# STM32F103ZET6.net
KiCad netlist of a schematic drawn in Altium Designer
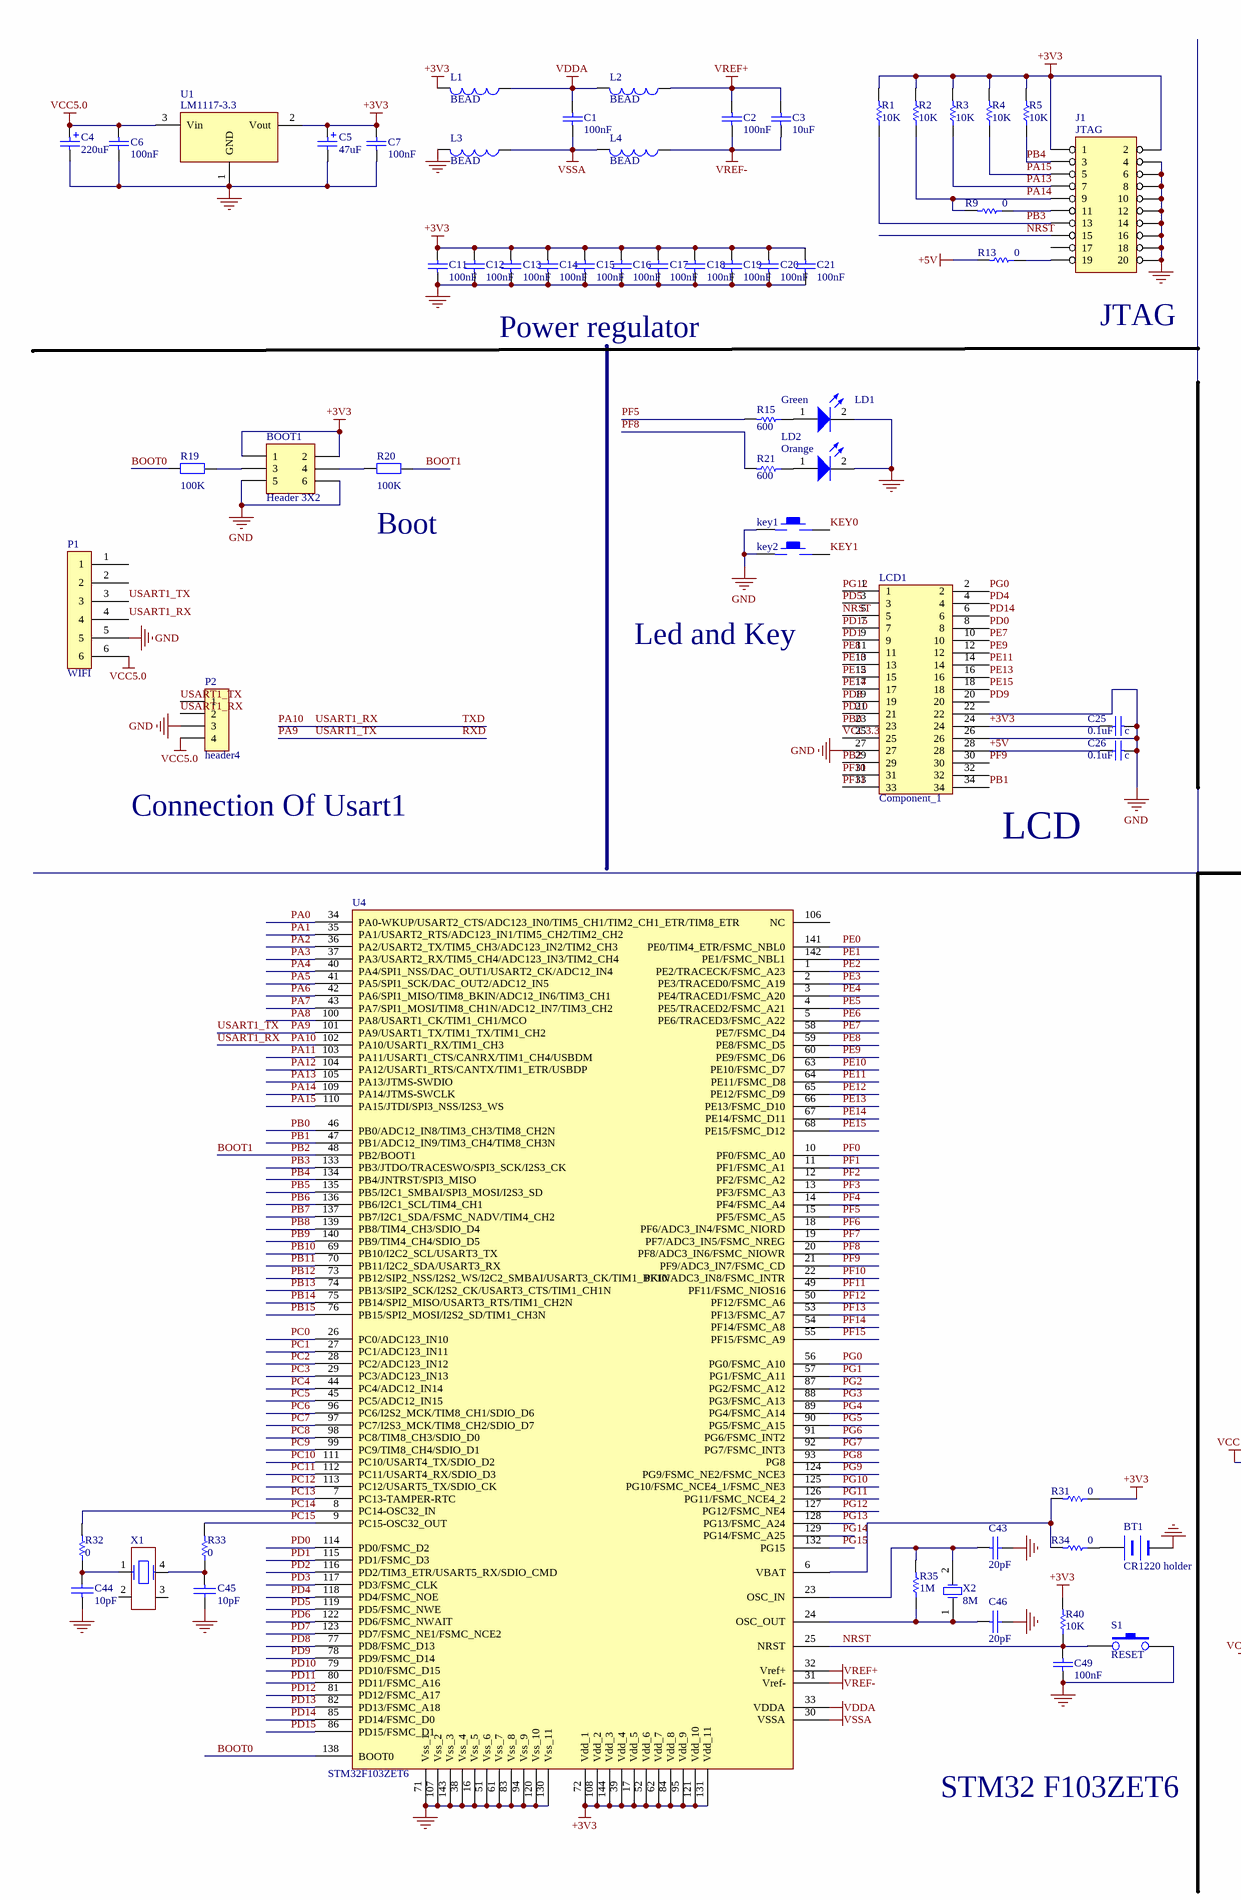
[diagram p0: STM32F103ZET6.SCHDOC, left]
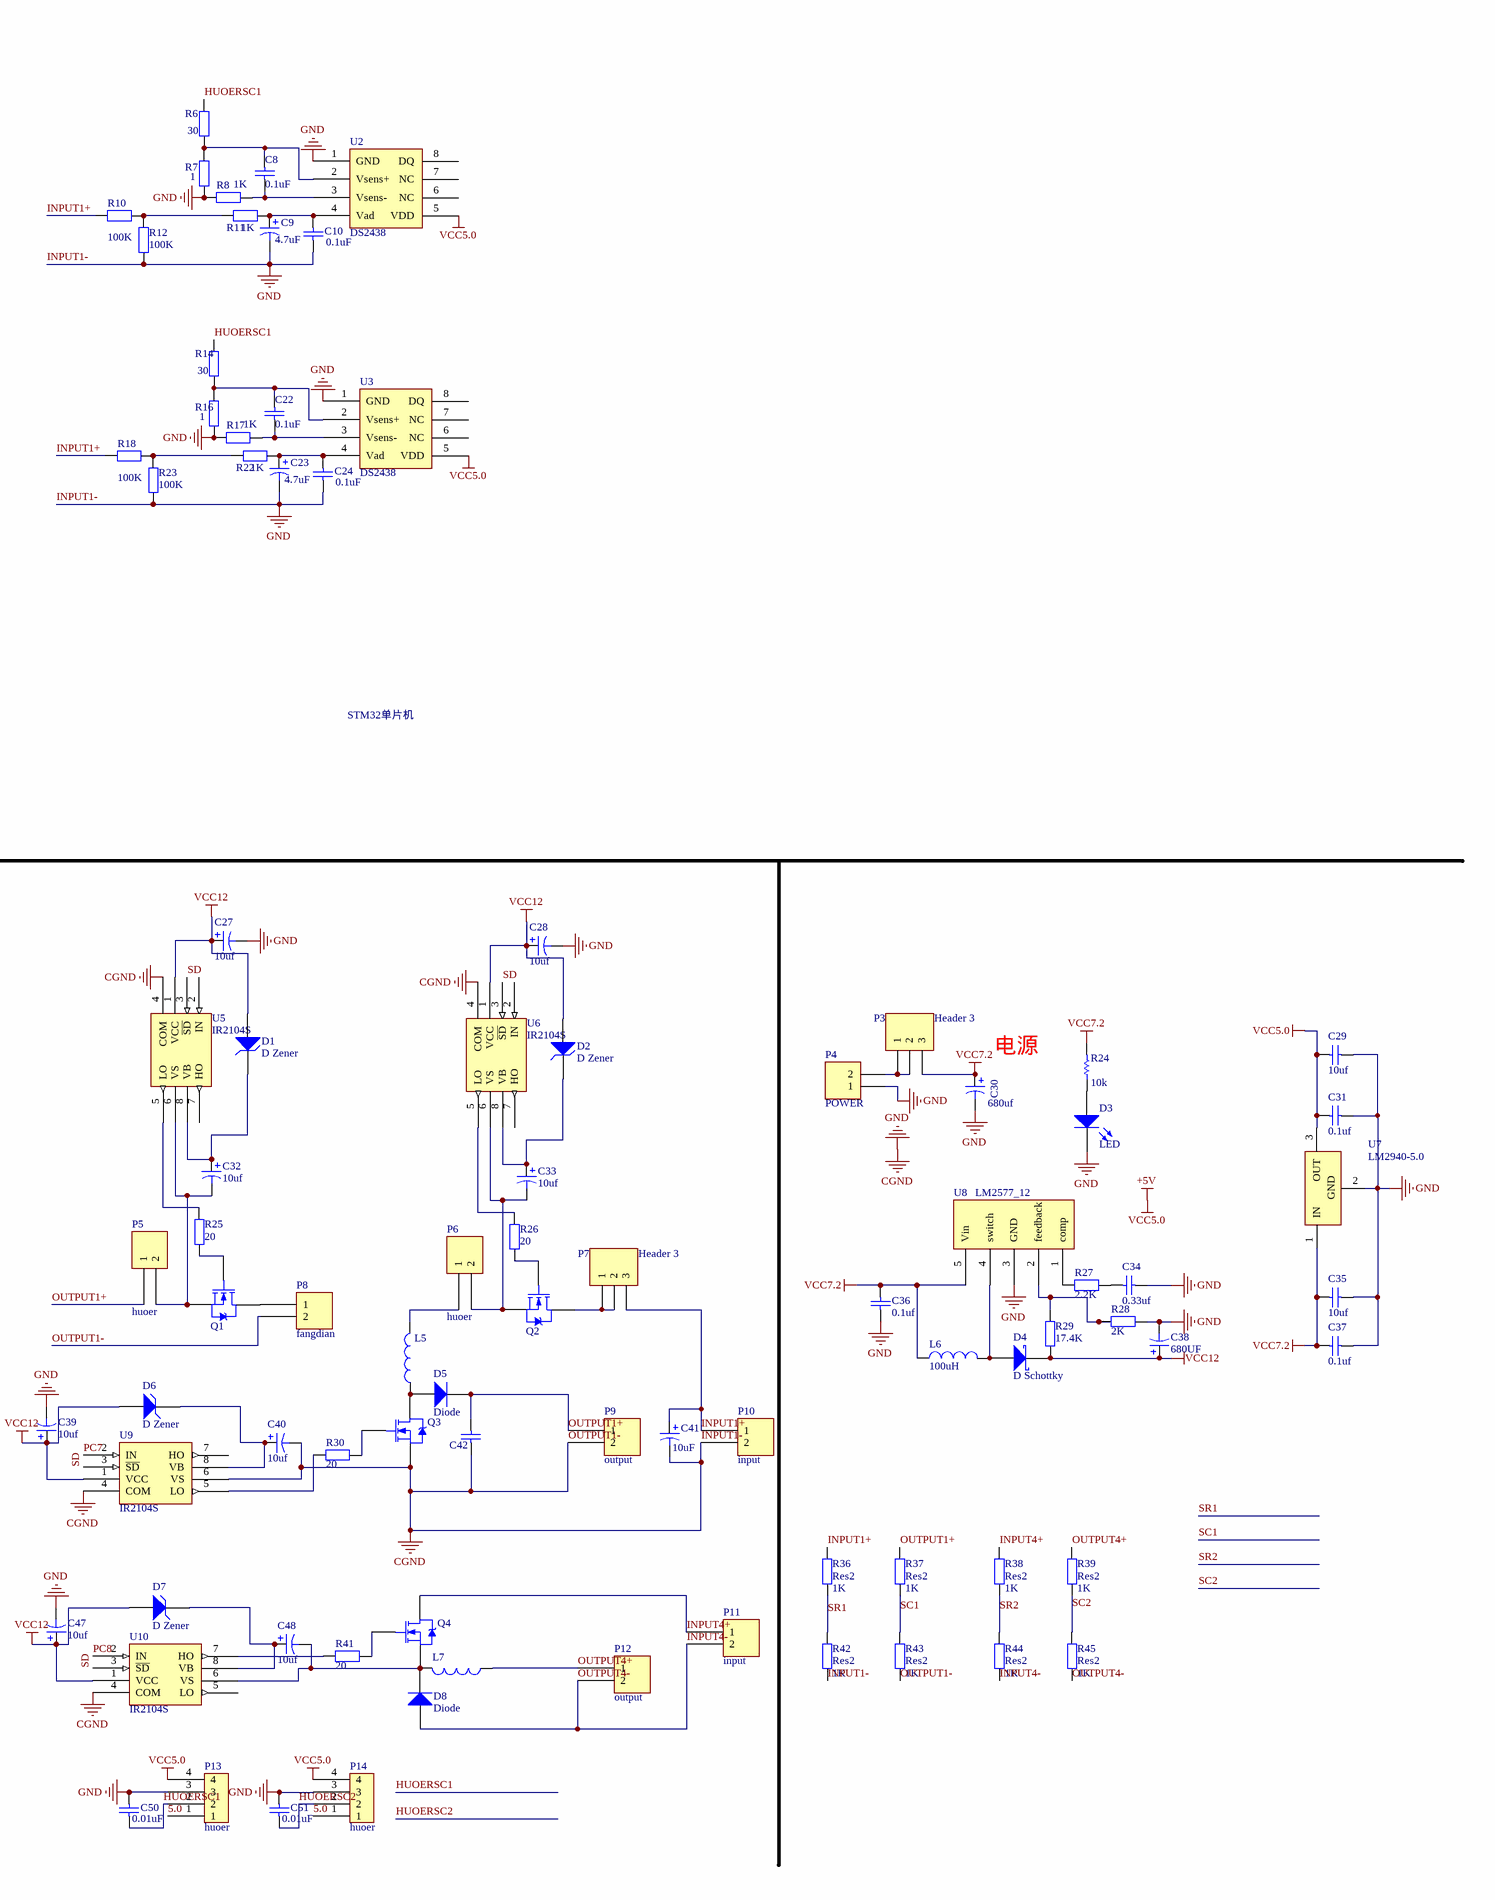
[diagram p1: STM32F103ZET6.SCHDOC, right]

(export (version "E")
  (design (tool "Eeschema 10.0.6"))
  (components
    (comp (ref "BOOT1")
      (value "Header 3X2")
      (footprint "HDR2X3")
      (description "Header, 3-Pin, Dual row")
      (fields (field (name "PUBLISHER") "*"))
      (libsource (lib "WARSHIP_SCH") (part "Header 3X2"))
    )
    (comp (ref "BT1")
      (value "CR1220 holder")
      (footprint "BAT")
      (description "Battery")
      (libsource (lib "*") (part "BATTERY"))
    )
    (comp (ref "C1")
      (value "100nF")
      (footprint "0805C")
      (description "Capacitor")
      (fields (field (name "PUBLISHER") "Altium Limited"))
      (libsource (lib "Miscellaneous Devices") (part "Cap"))
    )
    (comp (ref "C2")
      (value "100nF")
      (footprint "0805C")
      (description "Capacitor")
      (fields (field (name "PUBLISHER") "Altium Limited"))
      (libsource (lib "Miscellaneous Devices") (part "Cap"))
    )
    (comp (ref "C3")
      (value "10uF")
      (footprint "0805C")
      (description "Capacitor")
      (fields (field (name "PUBLISHER") "Altium Limited"))
      (libsource (lib "Miscellaneous Devices") (part "Cap"))
    )
    (comp (ref "C4")
      (value "220uF")
      (footprint "0805C")
      (description "Polarized Capacitor (Radial)")
      (fields (field (name "PUBLISHER") "Altium Limited"))
      (libsource (lib "") (part "Cap Pol1_1"))
    )
    (comp (ref "C5")
      (value "47uF")
      (footprint "0805C")
      (description "Polarized Capacitor (Radial)")
      (fields (field (name "PUBLISHER") "Altium Limited"))
      (libsource (lib "") (part "Cap Pol1_1"))
    )
    (comp (ref "C6")
      (value "100nF")
      (footprint "0805C")
      (description "Capacitor")
      (fields (field (name "PUBLISHER") "Altium Limited"))
      (libsource (lib "Miscellaneous Devices") (part "Cap"))
    )
    (comp (ref "C7")
      (value "100nF")
      (footprint "0805C")
      (description "Capacitor")
      (fields (field (name "PUBLISHER") "Altium Limited"))
      (libsource (lib "Miscellaneous Devices") (part "Cap"))
    )
    (comp (ref "C8")
      (value "0.1uF")
      (footprint "0805C")
      (description "Capacitor")
      (fields (field (name "PUBLISHER") "Altium Limited"))
      (libsource (lib "Miscellaneous Devices") (part "Cap"))
    )
    (comp (ref "C9")
      (value "4.7uF")
      (footprint "0805C")
      (description "Polarized Capacitor (Radial)")
      (fields (field (name "PUBLISHER") "Altium Limited"))
      (libsource (lib "Miscellaneous Devices") (part "Cap Pol1"))
    )
    (comp (ref "C10")
      (value "0.1uF")
      (footprint "0805C")
      (description "Capacitor")
      (fields (field (name "PUBLISHER") "Altium Limited"))
      (libsource (lib "Miscellaneous Devices") (part "Cap"))
    )
    (comp (ref "C11")
      (value "100nF")
      (footprint "0805C")
      (description "Capacitor")
      (fields (field (name "PUBLISHER") "Altium Limited"))
      (libsource (lib "Miscellaneous Devices") (part "CAP"))
    )
    (comp (ref "C12")
      (value "100nF")
      (footprint "0805C")
      (description "Capacitor")
      (fields (field (name "PUBLISHER") "Altium Limited"))
      (libsource (lib "Miscellaneous Devices") (part "CAP"))
    )
    (comp (ref "C13")
      (value "100nF")
      (footprint "0805C")
      (description "Capacitor")
      (fields (field (name "PUBLISHER") "Altium Limited"))
      (libsource (lib "Miscellaneous Devices") (part "CAP"))
    )
    (comp (ref "C14")
      (value "100nF")
      (footprint "0805C")
      (description "Capacitor")
      (fields (field (name "PUBLISHER") "Altium Limited"))
      (libsource (lib "Miscellaneous Devices") (part "CAP"))
    )
    (comp (ref "C15")
      (value "100nF")
      (footprint "0805C")
      (description "Capacitor")
      (fields (field (name "PUBLISHER") "Altium Limited"))
      (libsource (lib "Miscellaneous Devices") (part "CAP"))
    )
    (comp (ref "C16")
      (value "100nF")
      (footprint "0805C")
      (description "Capacitor")
      (fields (field (name "PUBLISHER") "Altium Limited"))
      (libsource (lib "Miscellaneous Devices") (part "CAP"))
    )
    (comp (ref "C17")
      (value "100nF")
      (footprint "0805C")
      (description "Capacitor")
      (fields (field (name "PUBLISHER") "Altium Limited"))
      (libsource (lib "Miscellaneous Devices") (part "CAP"))
    )
    (comp (ref "C18")
      (value "100nF")
      (footprint "0805C")
      (description "Capacitor")
      (fields (field (name "PUBLISHER") "Altium Limited"))
      (libsource (lib "Miscellaneous Devices") (part "CAP"))
    )
    (comp (ref "C19")
      (value "100nF")
      (footprint "0805C")
      (description "Capacitor")
      (fields (field (name "PUBLISHER") "Altium Limited"))
      (libsource (lib "Miscellaneous Devices") (part "CAP"))
    )
    (comp (ref "C20")
      (value "100nF")
      (footprint "0805C")
      (description "Capacitor")
      (fields (field (name "PUBLISHER") "Altium Limited"))
      (libsource (lib "Miscellaneous Devices") (part "CAP"))
    )
    (comp (ref "C21")
      (value "100nF")
      (footprint "0805C")
      (description "Capacitor")
      (fields (field (name "PUBLISHER") "Altium Limited"))
      (libsource (lib "Miscellaneous Devices") (part "CAP"))
    )
    (comp (ref "C22")
      (value "0.1uF")
      (footprint "0805C")
      (description "Capacitor")
      (fields (field (name "PUBLISHER") "Altium Limited"))
      (libsource (lib "Miscellaneous Devices") (part "Cap"))
    )
    (comp (ref "C23")
      (value "4.7uF")
      (footprint "0805C")
      (description "Polarized Capacitor (Radial)")
      (fields (field (name "PUBLISHER") "Altium Limited"))
      (libsource (lib "Miscellaneous Devices") (part "Cap Pol1"))
    )
    (comp (ref "C24")
      (value "0.1uF")
      (footprint "0805C")
      (description "Capacitor")
      (fields (field (name "PUBLISHER") "Altium Limited"))
      (libsource (lib "Miscellaneous Devices") (part "Cap"))
    )
    (comp (ref "C25")
      (value "c")
      (footprint "0805C")
      (description "Capacitor")
      (fields (field (name "ALTIUM_VALUE") "0.1uF") (field (name "PUBLISHER") "Altium Limited"))
      (libsource (lib "Miscellaneous Devices") (part "Cap"))
    )
    (comp (ref "C26")
      (value "c")
      (footprint "0805C")
      (description "Capacitor")
      (fields (field (name "ALTIUM_VALUE") "0.1uF") (field (name "PUBLISHER") "Altium Limited"))
      (libsource (lib "Miscellaneous Devices") (part "Cap"))
    )
    (comp (ref "C27")
      (value "10uf")
      (footprint "0805C")
      (description "Polarized Capacitor (Surface Mount)")
      (fields (field (name "Comment") "Cap Pol3") (field (name "PUBLISHER") "Altium Limited"))
      (libsource (lib "Miscellaneous Devices") (part "Cap Pol3"))
    )
    (comp (ref "C28")
      (value "10uf")
      (footprint "0805C")
      (description "Polarized Capacitor (Surface Mount)")
      (fields (field (name "Comment") "Cap Pol3") (field (name "PUBLISHER") "Altium Limited"))
      (libsource (lib "Miscellaneous Devices") (part "Cap Pol3"))
    )
    (comp (ref "C29")
      (value "10uf")
      (footprint "0805C")
      (description "Capacitor")
      (fields (field (name "Comment") "Cap") (field (name "PUBLISHER") "Altium Limited"))
      (libsource (lib "Miscellaneous Devices") (part "Cap"))
    )
    (comp (ref "C30")
      (value "680uf")
      (footprint "cap")
      (description "Polarized Capacitor (Radial)")
      (fields (field (name "Comment") "Cap Pol1") (field (name "PUBLISHER") "Altium Limited"))
      (libsource (lib "Miscellaneous Devices") (part "Cap Pol1"))
    )
    (comp (ref "C31")
      (value "0.1uf")
      (footprint "0805C")
      (description "Capacitor")
      (fields (field (name "Comment") "Cap") (field (name "PUBLISHER") "Altium Limited"))
      (libsource (lib "Miscellaneous Devices") (part "Cap"))
    )
    (comp (ref "C32")
      (value "10uf")
      (footprint "0805C")
      (description "Polarized Capacitor (Surface Mount)")
      (fields (field (name "Comment") "Cap Pol3") (field (name "PUBLISHER") "Altium Limited"))
      (libsource (lib "Miscellaneous Devices") (part "Cap Pol3"))
    )
    (comp (ref "C33")
      (value "10uf")
      (footprint "0805C")
      (description "Polarized Capacitor (Surface Mount)")
      (fields (field (name "Comment") "Cap Pol3") (field (name "PUBLISHER") "Altium Limited"))
      (libsource (lib "Miscellaneous Devices") (part "Cap Pol3"))
    )
    (comp (ref "C34")
      (value "0.33uf")
      (footprint "0805C")
      (description "Capacitor (Semiconductor SIM Model)")
      (fields (field (name "Comment") "Cap Semi") (field (name "PUBLISHER") "Altium Limited"))
      (libsource (lib "Miscellaneous Devices") (part "Cap Semi"))
    )
    (comp (ref "C35")
      (value "10uf")
      (footprint "0805C")
      (description "Capacitor")
      (fields (field (name "Comment") "Cap") (field (name "PUBLISHER") "Altium Limited"))
      (libsource (lib "Miscellaneous Devices") (part "Cap"))
    )
    (comp (ref "C36")
      (value "0.1uf")
      (footprint "0805C")
      (description "Capacitor (Semiconductor SIM Model)")
      (fields (field (name "Comment") "Cap Semi") (field (name "PUBLISHER") "Altium Limited"))
      (libsource (lib "Miscellaneous Devices") (part "Cap Semi"))
    )
    (comp (ref "C37")
      (value "0.1uf")
      (footprint "0805C")
      (description "Capacitor")
      (fields (field (name "Comment") "Cap") (field (name "PUBLISHER") "Altium Limited"))
      (libsource (lib "Miscellaneous Devices") (part "Cap"))
    )
    (comp (ref "C38")
      (value "680UF")
      (footprint "cap")
      (description "Polarized Capacitor (Surface Mount)")
      (fields (field (name "Comment") "Cap Pol3") (field (name "PUBLISHER") "Altium Limited"))
      (libsource (lib "Miscellaneous Devices") (part "Cap Pol3"))
    )
    (comp (ref "C39")
      (value "10uf")
      (footprint "0805C")
      (description "Polarized Capacitor (Surface Mount)")
      (fields (field (name "Comment") "Cap Pol3") (field (name "PUBLISHER") "Altium Limited"))
      (libsource (lib "Miscellaneous Devices") (part "Cap Pol3"))
    )
    (comp (ref "C40")
      (value "10uf")
      (footprint "0805C")
      (description "Polarized Capacitor (Surface Mount)")
      (fields (field (name "Comment") "Cap Pol3") (field (name "PUBLISHER") "Altium Limited"))
      (libsource (lib "Miscellaneous Devices") (part "Cap Pol3"))
    )
    (comp (ref "C41")
      (value "10uF")
      (footprint "0805C")
      (description "Polarized Capacitor (Radial)")
      (fields (field (name "PUBLISHER") "Altium Limited"))
      (libsource (lib "Miscellaneous Devices") (part "Cap Pol1"))
    )
    (comp (ref "C42")
      (value "~")
      (footprint "cap")
      (description "Capacitor")
      (fields (field (name "PUBLISHER") "Altium Limited"))
      (libsource (lib "Miscellaneous Devices") (part "Cap"))
    )
    (comp (ref "C43")
      (value "20pF")
      (footprint "0805C")
      (description "Capacitor")
      (libsource (lib "*") (part "CAP"))
    )
    (comp (ref "C44")
      (value "10pF")
      (footprint "0805C")
      (description "Capacitor")
      (libsource (lib "") (part "CAP_1"))
    )
    (comp (ref "C45")
      (value "10pF")
      (footprint "0805C")
      (description "Capacitor")
      (libsource (lib "") (part "CAP_1"))
    )
    (comp (ref "C46")
      (value "20pF")
      (footprint "0805C")
      (description "Capacitor")
      (libsource (lib "*") (part "CAP"))
    )
    (comp (ref "C47")
      (value "10uf")
      (footprint "0805C")
      (description "Polarized Capacitor (Surface Mount)")
      (fields (field (name "Comment") "Cap Pol3") (field (name "PUBLISHER") "Altium Limited"))
      (libsource (lib "Miscellaneous Devices") (part "Cap Pol3"))
    )
    (comp (ref "C48")
      (value "10uf")
      (footprint "0805C")
      (description "Polarized Capacitor (Surface Mount)")
      (fields (field (name "Comment") "Cap Pol3") (field (name "PUBLISHER") "Altium Limited"))
      (libsource (lib "Miscellaneous Devices") (part "Cap Pol3"))
    )
    (comp (ref "C49")
      (value "100nF")
      (footprint "0805C")
      (description "Capacitor")
      (fields (field (name "PUBLISHER") "Altium Limited"))
      (libsource (lib "Miscellaneous Devices") (part "CAP"))
    )
    (comp (ref "C50")
      (value "0.01uF")
      (footprint "0805C")
      (description "Capacitor")
      (fields (field (name "PUBLISHER") "Altium Limited"))
      (libsource (lib "Miscellaneous Devices") (part "Cap"))
    )
    (comp (ref "C51")
      (value "0.01uF")
      (footprint "0805C")
      (description "Capacitor")
      (fields (field (name "PUBLISHER") "Altium Limited"))
      (libsource (lib "Miscellaneous Devices") (part "Cap"))
    )
    (comp (ref "D1")
      (value "D Zener")
      (footprint "SMB")
      (description "Zener Diode")
      (fields (field (name "PUBLISHER") "Altium Limited"))
      (libsource (lib "Miscellaneous Devices") (part "D Zener"))
    )
    (comp (ref "D2")
      (value "D Zener")
      (footprint "SMB")
      (description "Zener Diode")
      (fields (field (name "PUBLISHER") "Altium Limited"))
      (libsource (lib "Miscellaneous Devices") (part "D Zener"))
    )
    (comp (ref "D3")
      (value "LED")
      (footprint "0805D")
      (description "Typical RED, GREEN, YELLOW, AMBER GaAs LED")
      (fields (field (name "PUBLISHER") "Altium Limited"))
      (libsource (lib "") (part "LED2_1"))
    )
    (comp (ref "D4")
      (value "D Schottky")
      (footprint "SMB")
      (description "Schottky Diode")
      (fields (field (name "PUBLISHER") "Altium Limited"))
      (libsource (lib "Miscellaneous Devices") (part "D Schottky"))
    )
    (comp (ref "D5")
      (value "Diode")
      (footprint "SMB")
      (description "Default Diode")
      (fields (field (name "PUBLISHER") "Altium Limited"))
      (libsource (lib "Miscellaneous Devices") (part "Diode"))
    )
    (comp (ref "D6")
      (value "D Zener")
      (footprint "SMB")
      (description "Zener Diode")
      (fields (field (name "PUBLISHER") "Altium Limited"))
      (libsource (lib "Miscellaneous Devices") (part "D Zener"))
    )
    (comp (ref "D7")
      (value "D Zener")
      (footprint "SMB")
      (description "Zener Diode")
      (fields (field (name "PUBLISHER") "Altium Limited"))
      (libsource (lib "Miscellaneous Devices") (part "D Zener"))
    )
    (comp (ref "D8")
      (value "Diode")
      (footprint "SMB")
      (description "Default Diode")
      (fields (field (name "PUBLISHER") "Altium Limited"))
      (libsource (lib "Miscellaneous Devices") (part "Diode"))
    )
    (comp (ref "J1") (value "JTAG") (footprint "JTAG_20PIN") (libsource (lib "*") (part "HEADER 10X2")))
    (comp (ref "key1") (value "KEY_M") (footprint "key_2pin") (libsource (lib "WARSHIP_SCH") (part "KEY_M")))
    (comp (ref "key2") (value "KEY_M") (footprint "key_2pin") (libsource (lib "WARSHIP_SCH") (part "KEY_M")))
    (comp (ref "L1")
      (value "BEAD")
      (footprint "0805R")
      (description "Inductor")
      (fields (field (name "PUBLISHER") "Altium Limited"))
      (libsource (lib "Miscellaneous Devices") (part "Inductor"))
    )
    (comp (ref "L2")
      (value "BEAD")
      (footprint "0805R")
      (description "Inductor")
      (fields (field (name "PUBLISHER") "Altium Limited"))
      (libsource (lib "Miscellaneous Devices") (part "Inductor"))
    )
    (comp (ref "L3")
      (value "BEAD")
      (footprint "0805R")
      (description "Inductor")
      (fields (field (name "PUBLISHER") "Altium Limited"))
      (libsource (lib "Miscellaneous Devices") (part "Inductor"))
    )
    (comp (ref "L4")
      (value "BEAD")
      (footprint "0805R")
      (description "Inductor")
      (fields (field (name "PUBLISHER") "Altium Limited"))
      (libsource (lib "Miscellaneous Devices") (part "Inductor"))
    )
    (comp (ref "L5")
      (value "~")
      (footprint "L1")
      (description "Inductor")
      (fields (field (name "PUBLISHER") "Altium Limited"))
      (libsource (lib "Miscellaneous Devices") (part "Inductor"))
    )
    (comp (ref "L6")
      (value "100uH")
      (footprint "L1")
      (description "Inductor")
      (fields (field (name "PUBLISHER") "Altium Limited"))
      (libsource (lib "主控板") (part "Inductor"))
    )
    (comp (ref "L7")
      (value "~")
      (footprint "L1")
      (description "Inductor")
      (fields (field (name "PUBLISHER") "Altium Limited"))
      (libsource (lib "Miscellaneous Devices") (part "Inductor"))
    )
    (comp (ref "LCD1")
      (value "Component_1")
      (footprint "LCD")
      (libsource (lib "Schlib1") (part "Component_1"))
    )
    (comp (ref "LD1")
      (value "Green")
      (footprint "0805D")
      (description "Typical RED, GREEN, YELLOW, AMBER GaAs LED")
      (fields (field (name "PUBLISHER") "Altium Limited"))
      (libsource (lib "Miscellaneous Devices") (part "LED2"))
    )
    (comp (ref "LD2")
      (value "Orange")
      (footprint "0805D")
      (description "Typical RED, GREEN, YELLOW, AMBER GaAs LED")
      (fields (field (name "PUBLISHER") "Altium Limited"))
      (libsource (lib "Miscellaneous Devices") (part "LED2"))
    )
    (comp (ref "P1") (value "WIFI") (footprint "wifi") (libsource (lib "Schlib1") (part "WIFI")))
    (comp (ref "P2")
      (value "header4")
      (footprint "HEADER4-PS")
      (libsource (lib "PCB_Project1") (part "header4"))
    )
    (comp (ref "P3")
      (value "Header 3")
      (footprint "header3-power")
      (description "Header, 3-Pin")
      (fields (field (name "PUBLISHER") "Altium Limited"))
      (libsource (lib "Miscellaneous Connectors") (part "Header 3"))
    )
    (comp (ref "P4")
      (value "POWER")
      (footprint "dianji")
      (description "Header, 2-Pin")
      (fields (field (name "PUBLISHER") "Altium Limited"))
      (libsource (lib "Miscellaneous Connectors") (part "Header 2"))
    )
    (comp (ref "P5") (value "huoer") (footprint "huoer1") (libsource (lib "") (part "Header2_1")))
    (comp (ref "P6") (value "huoer") (footprint "huoer1") (libsource (lib "") (part "Header2_1")))
    (comp (ref "P7")
      (value "Header 3")
      (footprint "header3-power")
      (description "Header, 3-Pin")
      (fields (field (name "PUBLISHER") "Altium Limited"))
      (libsource (lib "Miscellaneous Connectors") (part "Header 3"))
    )
    (comp (ref "P8") (value "fangdian") (footprint "duanzi2-5mm") (libsource (lib "桥") (part "Header2")))
    (comp (ref "P9") (value "output") (footprint "duanzi2-5mm") (libsource (lib "桥") (part "Header2")))
    (comp (ref "P10") (value "input") (footprint "duanzi2-5mm") (libsource (lib "桥") (part "Header2")))
    (comp (ref "P11") (value "input") (footprint "duanzi2-5mm") (libsource (lib "桥") (part "Header2")))
    (comp (ref "P12") (value "output") (footprint "duanzi2-5mm") (libsource (lib "桥") (part "Header2")))
    (comp (ref "P13") (value "huoer") (footprint "huoer") (libsource (lib "") (part "huoer_1")))
    (comp (ref "P14") (value "huoer") (footprint "huoer") (libsource (lib "") (part "huoer_1")))
    (comp (ref "Q1")
      (value "AOD4184")
      (footprint "mos3205")
      (description "N-Channel Power MOSFET")
      (fields (field (name "PUBLISHER") "Altium Limited"))
      (libsource (lib "Miscellaneous Devices") (part "NMOS-2"))
    )
    (comp (ref "Q2")
      (value "AOD4184")
      (footprint "mos3205")
      (description "N-Channel Power MOSFET")
      (fields (field (name "PUBLISHER") "Altium Limited"))
      (libsource (lib "Miscellaneous Devices") (part "NMOS-2"))
    )
    (comp (ref "Q3")
      (value "AOD4184")
      (footprint "mos3205")
      (description "N-Channel Power MOSFET")
      (fields (field (name "PUBLISHER") "Altium Limited"))
      (libsource (lib "Miscellaneous Devices") (part "NMOS-2"))
    )
    (comp (ref "Q4")
      (value "AOD4184")
      (footprint "mos3205")
      (description "N-Channel Power MOSFET")
      (fields (field (name "PUBLISHER") "Altium Limited"))
      (libsource (lib "Miscellaneous Devices") (part "NMOS-2"))
    )
    (comp (ref "R1")
      (value "10K")
      (footprint "0805R")
      (description "Resistor")
      (fields (field (name "PUBLISHER") "Altium Limited"))
      (libsource (lib "Miscellaneous Devices") (part "Res1"))
    )
    (comp (ref "R2")
      (value "10K")
      (footprint "0805R")
      (description "Resistor")
      (fields (field (name "PUBLISHER") "Altium Limited"))
      (libsource (lib "Miscellaneous Devices") (part "Res1"))
    )
    (comp (ref "R3")
      (value "10K")
      (footprint "0805R")
      (description "Resistor")
      (fields (field (name "PUBLISHER") "Altium Limited"))
      (libsource (lib "Miscellaneous Devices") (part "Res1"))
    )
    (comp (ref "R4")
      (value "10K")
      (footprint "0805R")
      (description "Resistor")
      (fields (field (name "PUBLISHER") "Altium Limited"))
      (libsource (lib "Miscellaneous Devices") (part "Res1"))
    )
    (comp (ref "R5")
      (value "10K")
      (footprint "0805R")
      (description "Resistor")
      (fields (field (name "PUBLISHER") "Altium Limited"))
      (libsource (lib "Miscellaneous Devices") (part "Res1"))
    )
    (comp (ref "R6")
      (value "30")
      (footprint "0805R")
      (description "Resistor")
      (fields (field (name "PUBLISHER") "Altium Limited"))
      (libsource (lib "Miscellaneous Devices") (part "Res2"))
    )
    (comp (ref "R7")
      (value "1")
      (footprint "0805R")
      (description "Resistor")
      (fields (field (name "PUBLISHER") "Altium Limited"))
      (libsource (lib "Miscellaneous Devices") (part "Res2"))
    )
    (comp (ref "R8")
      (value "1K")
      (footprint "0805R")
      (description "Resistor")
      (fields (field (name "PUBLISHER") "Altium Limited"))
      (libsource (lib "") (part "Res2_1"))
    )
    (comp (ref "R9")
      (value "0")
      (footprint "0805R")
      (description "Resistor")
      (fields (field (name "PUBLISHER") "Altium Limited"))
      (libsource (lib "Miscellaneous Devices") (part "Res1"))
    )
    (comp (ref "R10")
      (value "100K")
      (footprint "0805R")
      (description "Resistor")
      (fields (field (name "PUBLISHER") "Altium Limited"))
      (libsource (lib "") (part "Res2_2"))
    )
    (comp (ref "R11")
      (value "1K")
      (footprint "0805R")
      (description "Resistor")
      (fields (field (name "PUBLISHER") "Altium Limited"))
      (libsource (lib "") (part "Res2_1"))
    )
    (comp (ref "R12")
      (value "100K")
      (footprint "0805R")
      (description "Resistor")
      (fields (field (name "PUBLISHER") "Altium Limited"))
      (libsource (lib "Miscellaneous Devices") (part "Res2"))
    )
    (comp (ref "R13")
      (value "0")
      (footprint "0805R")
      (description "Resistor")
      (fields (field (name "PUBLISHER") "Altium Limited"))
      (libsource (lib "Miscellaneous Devices") (part "Res1"))
    )
    (comp (ref "R14")
      (value "30")
      (footprint "0805R")
      (description "Resistor")
      (fields (field (name "PUBLISHER") "Altium Limited"))
      (libsource (lib "Miscellaneous Devices") (part "Res2"))
    )
    (comp (ref "R15")
      (value "600")
      (footprint "0805R")
      (description "Resistor")
      (fields (field (name "PUBLISHER") "Altium Limited"))
      (libsource (lib "Miscellaneous Devices") (part "Res1"))
    )
    (comp (ref "R16")
      (value "1")
      (footprint "0805R")
      (description "Resistor")
      (fields (field (name "PUBLISHER") "Altium Limited"))
      (libsource (lib "Miscellaneous Devices") (part "Res2"))
    )
    (comp (ref "R17")
      (value "1K")
      (footprint "0805R")
      (description "Resistor")
      (fields (field (name "PUBLISHER") "Altium Limited"))
      (libsource (lib "") (part "Res2_1"))
    )
    (comp (ref "R18")
      (value "100K")
      (footprint "0805R")
      (description "Resistor")
      (fields (field (name "PUBLISHER") "Altium Limited"))
      (libsource (lib "") (part "Res2_2"))
    )
    (comp (ref "R19")
      (value "100K")
      (footprint "0805R")
      (description "Resistor")
      (fields (field (name "Comment") "Res2") (field (name "PUBLISHER") "Altium Limited"))
      (libsource (lib "") (part "Res2_1"))
    )
    (comp (ref "R20")
      (value "100K")
      (footprint "0805R")
      (description "Resistor")
      (fields (field (name "Comment") "Res2") (field (name "PUBLISHER") "Altium Limited"))
      (libsource (lib "") (part "Res2_1"))
    )
    (comp (ref "R21")
      (value "600")
      (footprint "0805R")
      (description "Resistor")
      (fields (field (name "PUBLISHER") "Altium Limited"))
      (libsource (lib "Miscellaneous Devices") (part "Res1"))
    )
    (comp (ref "R22")
      (value "1K")
      (footprint "0805R")
      (description "Resistor")
      (fields (field (name "PUBLISHER") "Altium Limited"))
      (libsource (lib "") (part "Res2_1"))
    )
    (comp (ref "R23")
      (value "100K")
      (footprint "0805R")
      (description "Resistor")
      (fields (field (name "PUBLISHER") "Altium Limited"))
      (libsource (lib "Miscellaneous Devices") (part "Res2"))
    )
    (comp (ref "R24")
      (value "10k")
      (footprint "0805R")
      (description "Resistor")
      (fields (field (name "Comment") "Res1") (field (name "PUBLISHER") "Altium Limited"))
      (libsource (lib "") (part "Res1_1"))
    )
    (comp (ref "R25")
      (value "20")
      (footprint "0805R")
      (description "Resistor")
      (fields (field (name "Comment") "Res2") (field (name "PUBLISHER") "Altium Limited"))
      (libsource (lib "") (part "Res2_3"))
    )
    (comp (ref "R26")
      (value "20")
      (footprint "0805R")
      (description "Resistor")
      (fields (field (name "Comment") "Res2") (field (name "PUBLISHER") "Altium Limited"))
      (libsource (lib "") (part "Res2_3"))
    )
    (comp (ref "R27")
      (value "2.2K")
      (footprint "0805R")
      (description "Resistor")
      (fields (field (name "Comment") "Res2") (field (name "PUBLISHER") "Altium Limited"))
      (libsource (lib "") (part "Res2_1"))
    )
    (comp (ref "R28")
      (value "2K")
      (footprint "0805R")
      (description "Resistor")
      (fields (field (name "Comment") "Res2") (field (name "PUBLISHER") "Altium Limited"))
      (libsource (lib "") (part "Res2_1"))
    )
    (comp (ref "R29")
      (value "17.4K")
      (footprint "0805R")
      (description "Resistor")
      (fields (field (name "Comment") "Res2") (field (name "PUBLISHER") "Altium Limited"))
      (libsource (lib "Miscellaneous Devices") (part "Res2"))
    )
    (comp (ref "R30")
      (value "20")
      (footprint "0805R")
      (description "Resistor")
      (fields (field (name "Comment") "Res2") (field (name "PUBLISHER") "Altium Limited"))
      (libsource (lib "") (part "Res2_1"))
    )
    (comp (ref "R31")
      (value "0")
      (footprint "0805R")
      (description "Resistor")
      (fields (field (name "PUBLISHER") "Altium Limited"))
      (libsource (lib "Miscellaneous Devices") (part "Res1"))
    )
    (comp (ref "R32")
      (value "0")
      (footprint "0805R")
      (description "Resistor")
      (fields (field (name "PUBLISHER") "Altium Limited"))
      (libsource (lib "Miscellaneous Devices") (part "Res1"))
    )
    (comp (ref "R33")
      (value "0")
      (footprint "0805R")
      (description "Resistor")
      (fields (field (name "PUBLISHER") "Altium Limited"))
      (libsource (lib "Miscellaneous Devices") (part "Res1"))
    )
    (comp (ref "R34")
      (value "0")
      (footprint "0805R")
      (description "Resistor")
      (fields (field (name "PUBLISHER") "Altium Limited"))
      (libsource (lib "Miscellaneous Devices") (part "Res1"))
    )
    (comp (ref "R35")
      (value "1M")
      (footprint "0805R")
      (description "Resistor")
      (fields (field (name "PUBLISHER") "Altium Limited"))
      (libsource (lib "Miscellaneous Devices") (part "Res1"))
    )
    (comp (ref "R36")
      (value "Res2")
      (footprint "0805R")
      (description "Resistor")
      (fields (field (name "ALTIUM_VALUE") "1K") (field (name "PUBLISHER") "Altium Limited"))
      (libsource (lib "Miscellaneous Devices") (part "Res2"))
    )
    (comp (ref "R37")
      (value "Res2")
      (footprint "0805R")
      (description "Resistor")
      (fields (field (name "ALTIUM_VALUE") "1K") (field (name "PUBLISHER") "Altium Limited"))
      (libsource (lib "Miscellaneous Devices") (part "Res2"))
    )
    (comp (ref "R38")
      (value "Res2")
      (footprint "0805R")
      (description "Resistor")
      (fields (field (name "ALTIUM_VALUE") "1K") (field (name "PUBLISHER") "Altium Limited"))
      (libsource (lib "Miscellaneous Devices") (part "Res2"))
    )
    (comp (ref "R39")
      (value "Res2")
      (footprint "0805R")
      (description "Resistor")
      (fields (field (name "ALTIUM_VALUE") "1K") (field (name "PUBLISHER") "Altium Limited"))
      (libsource (lib "Miscellaneous Devices") (part "Res2"))
    )
    (comp (ref "R40")
      (value "10K")
      (footprint "0805R")
      (description "Resistor")
      (fields (field (name "PUBLISHER") "Altium Limited"))
      (libsource (lib "Miscellaneous Devices") (part "res1"))
    )
    (comp (ref "R41")
      (value "20")
      (footprint "0805R")
      (description "Resistor")
      (fields (field (name "Comment") "Res2") (field (name "PUBLISHER") "Altium Limited"))
      (libsource (lib "") (part "Res2_1"))
    )
    (comp (ref "R42")
      (value "Res2")
      (footprint "0805R")
      (description "Resistor")
      (fields (field (name "ALTIUM_VALUE") "1K") (field (name "PUBLISHER") "Altium Limited"))
      (libsource (lib "Miscellaneous Devices") (part "Res2"))
    )
    (comp (ref "R43")
      (value "Res2")
      (footprint "0805R")
      (description "Resistor")
      (fields (field (name "ALTIUM_VALUE") "1K") (field (name "PUBLISHER") "Altium Limited"))
      (libsource (lib "Miscellaneous Devices") (part "Res2"))
    )
    (comp (ref "R44")
      (value "Res2")
      (footprint "0805R")
      (description "Resistor")
      (fields (field (name "ALTIUM_VALUE") "1K") (field (name "PUBLISHER") "Altium Limited"))
      (libsource (lib "Miscellaneous Devices") (part "Res2"))
    )
    (comp (ref "R45")
      (value "Res2")
      (footprint "0805R")
      (description "Resistor")
      (fields (field (name "ALTIUM_VALUE") "1K") (field (name "PUBLISHER") "Altium Limited"))
      (libsource (lib "Miscellaneous Devices") (part "Res2"))
    )
    (comp (ref "S1") (value "RESET") (footprint "key_2pin") (libsource (lib "*") (part "SW-PB")))
    (comp (ref "U1") (value "LM1117-3.3") (footprint "1117") (libsource (lib "*") (part "VOLTREG1")))
    (comp (ref "U2") (value "DS2438") (footprint "SOIC_8") (libsource (lib "Schlib1") (part "huoer")))
    (comp (ref "U3") (value "DS2438") (footprint "SOIC_8") (libsource (lib "Schlib1") (part "huoer")))
    (comp (ref "U4")
      (value "STM32F103ZET6")
      (footprint "TQFP144-B")
      (libsource (lib "STM32F103ZET6") (part "STM32F103ZET6"))
    )
    (comp (ref "U5") (value "IR2104S") (footprint "SOIC_8") (libsource (lib "") (part "IR2104S_1")))
    (comp (ref "U6") (value "IR2104S") (footprint "SOIC_8") (libsource (lib "") (part "IR2104S_1")))
    (comp (ref "U7")
      (value "LM2940-5.0")
      (footprint "TS3B_N")
      (description "1A Low Dropout Regulator")
      (fields
        (field (name "PARTNUMBER") "LM2940T-5.0")
        (field (name "MANUFACTURER") "National Semiconductor")
        (field (name "PUBLISHER") "Altium Limited")
      )
      (libsource (lib "NSC LDO") (part "LM2940T-5.0"))
    )
    (comp (ref "U8") (value "LM2577_12") (footprint "TS5B_N") (libsource (lib "桥") (part "LM2577_12")))
    (comp (ref "U9") (value "IR2104S") (footprint "SOIC_8") (libsource (lib "桥") (part "IR2104S")))
    (comp (ref "U10") (value "IR2104S") (footprint "SOIC_8") (libsource (lib "桥") (part "IR2104S")))
    (comp (ref "X1")
      (value "MC306-G-06Q-32.768 (manufacturer JFVNY)")
      (footprint "SM8")
      (libsource (lib "*") (part "MC306"))
    )
    (comp (ref "X2")
      (value "8M")
      (footprint "XTAL_US")
      (description "Crystal Oscillator")
      (fields (field (name "PUBLISHER") "*"))
      (libsource (lib "WARSHIP_SCH") (part "XTAL"))
    )
  )
  (nets
    (net (code "1") (name "+3V3") (class "Default")
      (node (ref "BOOT1") (pin "1") (pinfunction "1_1") (pintype "passive"))
      (node (ref "BOOT1") (pin "2") (pinfunction "2_2") (pintype "passive"))
      (node (ref "C11") (pin "1") (pinfunction "1_1") (pintype "passive"))
      (node (ref "C12") (pin "1") (pinfunction "1_1") (pintype "passive"))
      (node (ref "C13") (pin "1") (pinfunction "1_1") (pintype "passive"))
      (node (ref "C14") (pin "1") (pinfunction "1_1") (pintype "passive"))
      (node (ref "C15") (pin "1") (pinfunction "1_1") (pintype "passive"))
      (node (ref "C16") (pin "1") (pinfunction "1_1") (pintype "passive"))
      (node (ref "C17") (pin "1") (pinfunction "1_1") (pintype "passive"))
      (node (ref "C18") (pin "1") (pinfunction "1_1") (pintype "passive"))
      (node (ref "C19") (pin "1") (pinfunction "1_1") (pintype "passive"))
      (node (ref "C20") (pin "1") (pinfunction "1_1") (pintype "passive"))
      (node (ref "C21") (pin "1") (pinfunction "1_1") (pintype "passive"))
      (node (ref "C25") (pin "1") (pinfunction "1_1") (pintype "passive"))
      (node (ref "C5") (pin "1") (pinfunction "1_1") (pintype "passive"))
      (node (ref "C7") (pin "1") (pinfunction "1_1") (pintype "passive"))
      (node (ref "J1") (pin "1") (pinfunction "1_1") (pintype "passive"))
      (node (ref "J1") (pin "2") (pinfunction "2_2") (pintype "passive"))
      (node (ref "L1") (pin "2") (pinfunction "2_2") (pintype "passive"))
      (node (ref "LCD1") (pin "24") (pinfunction "24_24") (pintype "passive"))
      (node (ref "R1") (pin "2") (pinfunction "2_2") (pintype "passive"))
      (node (ref "R2") (pin "2") (pinfunction "2_2") (pintype "passive"))
      (node (ref "R3") (pin "2") (pinfunction "2_2") (pintype "passive"))
      (node (ref "R31") (pin "1") (pinfunction "1_1") (pintype "passive"))
      (node (ref "R4") (pin "2") (pinfunction "2_2") (pintype "passive"))
      (node (ref "R40") (pin "2") (pinfunction "2_2") (pintype "passive"))
      (node (ref "R5") (pin "2") (pinfunction "2_2") (pintype "passive"))
      (node (ref "U1") (pin "2") (pinfunction "Vout_2") (pintype "passive"))
      (node (ref "U4") (pin "108") (pinfunction "Vdd_2_108") (pintype "passive"))
      (node (ref "U4") (pin "121") (pinfunction "Vdd_10_121") (pintype "passive"))
      (node (ref "U4") (pin "131") (pinfunction "Vdd_11_131") (pintype "passive"))
      (node (ref "U4") (pin "144") (pinfunction "Vdd_3_144") (pintype "passive"))
      (node (ref "U4") (pin "17") (pinfunction "Vdd_5_17") (pintype "passive"))
      (node (ref "U4") (pin "39") (pinfunction "Vdd_4_39") (pintype "passive"))
      (node (ref "U4") (pin "52") (pinfunction "Vdd_6_52") (pintype "passive"))
      (node (ref "U4") (pin "62") (pinfunction "Vdd_7_62") (pintype "passive"))
      (node (ref "U4") (pin "72") (pinfunction "Vdd_1_72") (pintype "passive"))
      (node (ref "U4") (pin "84") (pinfunction "Vdd_8_84") (pintype "passive"))
      (node (ref "U4") (pin "95") (pinfunction "Vdd_9_95") (pintype "passive"))
    )
    (net (code "2") (name "+5V") (class "Default")
      (node (ref "C26") (pin "1") (pinfunction "1_1") (pintype "passive"))
      (node (ref "C29") (pin "2") (pinfunction "2_2") (pintype "passive"))
      (node (ref "C31") (pin "2") (pinfunction "2_2") (pintype "passive"))
      (node (ref "C4") (pin "1") (pinfunction "1_1") (pintype "passive"))
      (node (ref "C6") (pin "1") (pinfunction "1_1") (pintype "passive"))
      (node (ref "LCD1") (pin "28") (pinfunction "28_28") (pintype "passive"))
      (node (ref "P1") (pin "6") (pinfunction "6_6") (pintype "passive"))
      (node (ref "P13") (pin "4") (pinfunction "4_4") (pintype "passive"))
      (node (ref "P14") (pin "4") (pinfunction "4_4") (pintype "passive"))
      (node (ref "P2") (pin "4") (pinfunction "4_4") (pintype "passive"))
      (node (ref "R13") (pin "2") (pinfunction "2_2") (pintype "passive"))
      (node (ref "U1") (pin "3") (pinfunction "Vin_3") (pintype "passive"))
      (node (ref "U2") (pin "5") (pinfunction "VDD_5") (pintype "passive"))
      (node (ref "U3") (pin "5") (pinfunction "VDD_5") (pintype "passive"))
      (node (ref "U7") (pin "3") (pinfunction "OUT_3") (pintype "power_in"))
    )
    (net (code "3") (name "/5.0") (class "Default")
      (node (ref "P13") (pin "1") (pinfunction "1_1") (pintype "passive"))
      (node (ref "P14") (pin "1") (pinfunction "1_1") (pintype "passive"))
    )
    (net (code "4") (name "/BOOT0") (class "Default")
      (node (ref "R19") (pin "1") (pinfunction "1_1") (pintype "passive"))
      (node (ref "U4") (pin "138") (pinfunction "BOOT0_138") (pintype "passive"))
    )
    (net (code "5") (name "/BOOT1") (class "Default")
      (node (ref "LCD1") (pin "29") (pinfunction "29_29") (pintype "passive"))
      (node (ref "R20") (pin "2") (pinfunction "2_2") (pintype "passive"))
      (node (ref "U4") (pin "48") (pinfunction "PB2/BOOT1_48") (pintype "passive"))
    )
    (net (code "6") (name "/HUOERSC1") (class "Default")
      (node (ref "C50") (pin "1") (pinfunction "1_1") (pintype "passive"))
      (node (ref "P13") (pin "2") (pinfunction "2_2") (pintype "passive"))
      (node (ref "R14") (pin "2") (pinfunction "2_2") (pintype "passive"))
      (node (ref "R6") (pin "2") (pinfunction "2_2") (pintype "passive"))
    )
    (net (code "7") (name "/HUOERSC2") (class "Default")
      (node (ref "C51") (pin "1") (pinfunction "1_1") (pintype "passive"))
      (node (ref "P14") (pin "2") (pinfunction "2_2") (pintype "passive"))
    )
    (net (code "8") (name "/INPUT1+") (class "Default")
      (node (ref "C41") (pin "1") (pinfunction "1_1") (pintype "passive"))
      (node (ref "P10") (pin "1") (pinfunction "1_1") (pintype "passive"))
      (node (ref "P7") (pin "3") (pinfunction "3_3") (pintype "passive"))
      (node (ref "R10") (pin "2") (pinfunction "2_2") (pintype "passive"))
      (node (ref "R18") (pin "2") (pinfunction "2_2") (pintype "passive"))
      (node (ref "R36") (pin "2") (pinfunction "2_2") (pintype "passive"))
    )
    (net (code "9") (name "/INPUT4+") (class "Default")
      (node (ref "P11") (pin "1") (pinfunction "1_1") (pintype "passive"))
      (node (ref "Q4") (pin "2") (pinfunction "D_2") (pintype "passive"))
      (node (ref "R38") (pin "2") (pinfunction "2_2") (pintype "passive"))
    )
    (net (code "10") (name "/INPUT4-") (class "Default")
      (node (ref "D8") (pin "1") (pinfunction "A_1") (pintype "passive"))
      (node (ref "P11") (pin "2") (pinfunction "2_2") (pintype "passive"))
      (node (ref "P12") (pin "2") (pinfunction "2_2") (pintype "passive"))
      (node (ref "R44") (pin "1") (pinfunction "1_1") (pintype "passive"))
      (node (ref "R45") (pin "1") (pinfunction "1_1") (pintype "passive"))
    )
    (net (code "11") (name "/KEY0") (class "Default")
      (node (ref "key1") (pin "2") (pinfunction "2_2") (pintype "passive"))
    )
    (net (code "12") (name "/KEY1") (class "Default")
      (node (ref "key2") (pin "2") (pinfunction "2_2") (pintype "passive"))
    )
    (net (code "13") (name "/NRST") (class "Default")
      (node (ref "C49") (pin "2") (pinfunction "2_2") (pintype "passive"))
      (node (ref "J1") (pin "15") (pinfunction "15_15") (pintype "passive"))
      (node (ref "LCD1") (pin "5") (pinfunction "5_5") (pintype "passive"))
      (node (ref "R40") (pin "1") (pinfunction "1_1") (pintype "passive"))
      (node (ref "S1") (pin "1") (pinfunction "1_1") (pintype "passive"))
      (node (ref "U4") (pin "25") (pinfunction "NRST_25") (pintype "passive"))
    )
    (net (code "14") (name "/OUTPUT1+") (class "Default")
      (node (ref "C42") (pin "2") (pinfunction "2_2") (pintype "passive"))
      (node (ref "D5") (pin "2") (pinfunction "K_2") (pintype "passive"))
      (node (ref "P5") (pin "1") (pinfunction "1_1") (pintype "passive"))
      (node (ref "P9") (pin "1") (pinfunction "1_1") (pintype "passive"))
      (node (ref "R37") (pin "2") (pinfunction "2_2") (pintype "passive"))
    )
    (net (code "15") (name "/OUTPUT4+") (class "Default")
      (node (ref "L7") (pin "1") (pinfunction "1_1") (pintype "passive"))
      (node (ref "P12") (pin "1") (pinfunction "1_1") (pintype "passive"))
      (node (ref "R39") (pin "2") (pinfunction "2_2") (pintype "passive"))
    )
    (net (code "16") (name "/PA0") (class "Default")
      (node (ref "U4") (pin "34") (pinfunction "PA0-WKUP/USART2_CTS/ADC123_IN0/TIM5_CH1/TIM2_CH1_ETR/TIM8_ETR_34") (pintype "passive"))
    )
    (net (code "17") (name "/PA1") (class "Default")
      (node (ref "U4") (pin "35") (pinfunction "PA1/USART2_RTS/ADC123_IN1/TIM5_CH2/TIM2_CH2_35") (pintype "passive"))
    )
    (net (code "18") (name "/PA2") (class "Default")
      (node (ref "U4") (pin "36") (pinfunction "PA2/USART2_TX/TIM5_CH3/ADC123_IN2/TIM2_CH3_36") (pintype "passive"))
    )
    (net (code "19") (name "/PA3") (class "Default")
      (node (ref "U4") (pin "37") (pinfunction "PA3/USART2_RX/TIM5_CH4/ADC123_IN3/TIM2_CH4_37") (pintype "passive"))
    )
    (net (code "20") (name "/PA4") (class "Default")
      (node (ref "U4") (pin "40") (pinfunction "PA4/SPI1_NSS/DAC_OUT1/USART2_CK/ADC12_IN4_40") (pintype "passive"))
    )
    (net (code "21") (name "/PA5") (class "Default")
      (node (ref "U4") (pin "41") (pinfunction "PA5/SPI1_SCK/DAC_OUT2/ADC12_IN5_41") (pintype "passive"))
    )
    (net (code "22") (name "/PA6") (class "Default")
      (node (ref "U4") (pin "42") (pinfunction "PA6/SPI1_MISO/TIM8_BKIN/ADC12_IN6/TIM3_CH1_42") (pintype "passive"))
    )
    (net (code "23") (name "/PA7") (class "Default")
      (node (ref "U4") (pin "43") (pinfunction "PA7/SPI1_MOSI/TIM8_CH1N/ADC12_IN7/TIM3_CH2_43") (pintype "passive"))
    )
    (net (code "24") (name "/PA8") (class "Default")
      (node (ref "U4") (pin "100") (pinfunction "PA8/USART1_CK/TIM1_CH1/MCO_100") (pintype "passive"))
    )
    (net (code "25") (name "/PA9") (class "Default")
      (node (ref "P1") (pin "3") (pinfunction "3_3") (pintype "passive"))
      (node (ref "P2") (pin "1") (pinfunction "1_1") (pintype "passive"))
      (node (ref "U4") (pin "101") (pinfunction "PA9/USART1_TX/TIM1_TX/TIM1_CH2_101") (pintype "passive"))
    )
    (net (code "26") (name "/PA10") (class "Default")
      (node (ref "P1") (pin "4") (pinfunction "4_4") (pintype "passive"))
      (node (ref "P2") (pin "2") (pinfunction "2_2") (pintype "passive"))
      (node (ref "U4") (pin "102") (pinfunction "PA10/USART1_RX/TIM1_CH3_102") (pintype "passive"))
    )
    (net (code "27") (name "/PA11") (class "Default")
      (node (ref "U4") (pin "103") (pinfunction "PA11/USART1_CTS/CANRX/TIM1_CH4/USBDM_103") (pintype "passive"))
    )
    (net (code "28") (name "/PA12") (class "Default")
      (node (ref "U4") (pin "104") (pinfunction "PA12/USART1_RTS/CANTX/TIM1_ETR/USBDP_104") (pintype "passive"))
    )
    (net (code "29") (name "/PA13") (class "Default")
      (node (ref "J1") (pin "7") (pinfunction "7_7") (pintype "passive"))
      (node (ref "R3") (pin "1") (pinfunction "1_1") (pintype "passive"))
      (node (ref "U4") (pin "105") (pinfunction "PA13/JTMS-SWDIO_105") (pintype "passive"))
    )
    (net (code "30") (name "/PA14") (class "Default")
      (node (ref "J1") (pin "9") (pinfunction "9_9") (pintype "passive"))
      (node (ref "R2") (pin "1") (pinfunction "1_1") (pintype "passive"))
      (node (ref "R9") (pin "2") (pinfunction "2_2") (pintype "passive"))
      (node (ref "U4") (pin "109") (pinfunction "PA14/JTMS-SWCLK_109") (pintype "passive"))
    )
    (net (code "31") (name "/PA15") (class "Default")
      (node (ref "J1") (pin "5") (pinfunction "5_5") (pintype "passive"))
      (node (ref "R4") (pin "1") (pinfunction "1_1") (pintype "passive"))
      (node (ref "U4") (pin "110") (pinfunction "PA15/JTDI/SPI3_NSS/I2S3_WS_110") (pintype "passive"))
    )
    (net (code "32") (name "/PB0") (class "Default")
      (node (ref "LCD1") (pin "23") (pinfunction "23_23") (pintype "passive"))
      (node (ref "U4") (pin "46") (pinfunction "PB0/ADC12_IN8/TIM3_CH3/TIM8_CH2N_46") (pintype "passive"))
    )
    (net (code "33") (name "/PB1") (class "Default")
      (node (ref "LCD1") (pin "34") (pinfunction "34_34") (pintype "passive"))
      (node (ref "U4") (pin "47") (pinfunction "PB1/ADC12_IN9/TIM3_CH4/TIM8_CH3N_47") (pintype "passive"))
    )
    (net (code "34") (name "/PB3") (class "Default")
      (node (ref "J1") (pin "13") (pinfunction "13_13") (pintype "passive"))
      (node (ref "R1") (pin "1") (pinfunction "1_1") (pintype "passive"))
      (node (ref "U4") (pin "133") (pinfunction "PB3/JTDO/TRACESWO/SPI3_SCK/I2S3_CK_133") (pintype "passive"))
    )
    (net (code "35") (name "/PB4") (class "Default")
      (node (ref "J1") (pin "3") (pinfunction "3_3") (pintype "passive"))
      (node (ref "R5") (pin "1") (pinfunction "1_1") (pintype "passive"))
      (node (ref "U4") (pin "134") (pinfunction "PB4/JNTRST/SPI3_MISO_134") (pintype "passive"))
    )
    (net (code "36") (name "/PB5") (class "Default")
      (node (ref "U4") (pin "135") (pinfunction "PB5/I2C1_SMBAI/SPI3_MOSI/I2S3_SD_135") (pintype "passive"))
    )
    (net (code "37") (name "/PB6") (class "Default")
      (node (ref "U4") (pin "136") (pinfunction "PB6/I2C1_SCL/TIM4_CH1_136") (pintype "passive"))
    )
    (net (code "38") (name "/PB7") (class "Default")
      (node (ref "U4") (pin "137") (pinfunction "PB7/I2C1_SDA/FSMC_NADV/TIM4_CH2_137") (pintype "passive"))
    )
    (net (code "39") (name "/PB8") (class "Default")
      (node (ref "U4") (pin "139") (pinfunction "PB8/TIM4_CH3/SDIO_D4_139") (pintype "passive"))
    )
    (net (code "40") (name "/PB9") (class "Default")
      (node (ref "U4") (pin "140") (pinfunction "PB9/TIM4_CH4/SDIO_D5_140") (pintype "passive"))
    )
    (net (code "41") (name "/PB10") (class "Default")
      (node (ref "U4") (pin "69") (pinfunction "PB10/I2C2_SCL/USART3_TX_69") (pintype "passive"))
    )
    (net (code "42") (name "/PB11") (class "Default")
      (node (ref "U4") (pin "70") (pinfunction "PB11/I2C2_SDA/USART3_RX_70") (pintype "passive"))
    )
    (net (code "43") (name "/PB12") (class "Default")
      (node (ref "U4") (pin "73") (pinfunction "PB12/SIP2_NSS/I2S2_WS/I2C2_SMBAI/USART3_CK/TIM1_BKIN_73") (pintype "passive"))
    )
    (net (code "44") (name "/PB13") (class "Default")
      (node (ref "U4") (pin "74") (pinfunction "PB13/SIP2_SCK/I2S2_CK/USART3_CTS/TIM1_CH1N_74") (pintype "passive"))
    )
    (net (code "45") (name "/PB14") (class "Default")
      (node (ref "U4") (pin "75") (pinfunction "PB14/SPI2_MISO/USART3_RTS/TIM1_CH2N_75") (pintype "passive"))
    )
    (net (code "46") (name "/PB15") (class "Default")
      (node (ref "U4") (pin "76") (pinfunction "PB15/SPI2_MOSI/I2S2_SD/TIM1_CH3N_76") (pintype "passive"))
    )
    (net (code "47") (name "/PC0") (class "Default")
      (node (ref "U4") (pin "26") (pinfunction "PC0/ADC123_IN10_26") (pintype "passive"))
    )
    (net (code "48") (name "/PC1") (class "Default")
      (node (ref "U4") (pin "27") (pinfunction "PC1/ADC123_IN11_27") (pintype "passive"))
    )
    (net (code "49") (name "/PC2") (class "Default")
      (node (ref "U4") (pin "28") (pinfunction "PC2/ADC123_IN12_28") (pintype "passive"))
    )
    (net (code "50") (name "/PC3") (class "Default")
      (node (ref "U4") (pin "29") (pinfunction "PC3/ADC123_IN13_29") (pintype "passive"))
    )
    (net (code "51") (name "/PC4") (class "Default")
      (node (ref "U4") (pin "44") (pinfunction "PC4/ADC12_IN14_44") (pintype "passive"))
    )
    (net (code "52") (name "/PC5") (class "Default")
      (node (ref "U4") (pin "45") (pinfunction "PC5/ADC12_IN15_45") (pintype "passive"))
    )
    (net (code "53") (name "/PC6") (class "Default")
      (node (ref "U4") (pin "96") (pinfunction "PC6/I2S2_MCK/TIM8_CH1/SDIO_D6_96") (pintype "passive"))
    )
    (net (code "54") (name "/PC7") (class "Default")
      (node (ref "U4") (pin "97") (pinfunction "PC7/I2S3_MCK/TIM8_CH2/SDIO_D7_97") (pintype "passive"))
      (node (ref "U9") (pin "2") (pinfunction "IN_2") (pintype "input"))
    )
    (net (code "55") (name "/PC8") (class "Default")
      (node (ref "U10") (pin "2") (pinfunction "IN_2") (pintype "input"))
      (node (ref "U4") (pin "98") (pinfunction "PC8/TIM8_CH3/SDIO_D0_98") (pintype "passive"))
    )
    (net (code "56") (name "/PC9") (class "Default")
      (node (ref "U4") (pin "99") (pinfunction "PC9/TIM8_CH4/SDIO_D1_99") (pintype "passive"))
    )
    (net (code "57") (name "/PC10") (class "Default")
      (node (ref "U4") (pin "111") (pinfunction "PC10/USART4_TX/SDIO_D2_111") (pintype "passive"))
    )
    (net (code "58") (name "/PC11") (class "Default")
      (node (ref "U4") (pin "112") (pinfunction "PC11/USART4_RX/SDIO_D3_112") (pintype "passive"))
    )
    (net (code "59") (name "/PC12") (class "Default")
      (node (ref "U4") (pin "113") (pinfunction "PC12/USART5_TX/SDIO_CK_113") (pintype "passive"))
    )
    (net (code "60") (name "/PC13") (class "Default")
      (node (ref "U4") (pin "7") (pinfunction "PC13-TAMPER-RTC_7") (pintype "passive"))
    )
    (net (code "61") (name "/PC14") (class "Default")
      (node (ref "R32") (pin "2") (pinfunction "2_2") (pintype "passive"))
      (node (ref "U4") (pin "8") (pinfunction "PC14-OSC32_IN_8") (pintype "passive"))
    )
    (net (code "62") (name "/PC15") (class "Default")
      (node (ref "R33") (pin "2") (pinfunction "2_2") (pintype "passive"))
      (node (ref "U4") (pin "9") (pinfunction "PC15-OSC32_OUT_9") (pintype "passive"))
    )
    (net (code "63") (name "/PD0") (class "Default")
      (node (ref "LCD1") (pin "8") (pinfunction "8_8") (pintype "passive"))
      (node (ref "U4") (pin "114") (pinfunction "PD0/FSMC_D2_114") (pintype "passive"))
    )
    (net (code "64") (name "/PD1") (class "Default")
      (node (ref "LCD1") (pin "9") (pinfunction "9_9") (pintype "passive"))
      (node (ref "U4") (pin "115") (pinfunction "PD1/FSMC_D3_115") (pintype "passive"))
    )
    (net (code "65") (name "/PD2") (class "Default")
      (node (ref "U4") (pin "116") (pinfunction "PD2/TIM3_ETR/USART5_RX/SDIO_CMD_116") (pintype "passive"))
    )
    (net (code "66") (name "/PD3") (class "Default")
      (node (ref "U4") (pin "117") (pinfunction "PD3/FSMC_CLK_117") (pintype "passive"))
    )
    (net (code "67") (name "/PD4") (class "Default")
      (node (ref "LCD1") (pin "4") (pinfunction "4_4") (pintype "passive"))
      (node (ref "U4") (pin "118") (pinfunction "PD4/FSMC_NOE_118") (pintype "passive"))
    )
    (net (code "68") (name "/PD5") (class "Default")
      (node (ref "LCD1") (pin "3") (pinfunction "3_3") (pintype "passive"))
      (node (ref "U4") (pin "119") (pinfunction "PD5/FSMC_NWE_119") (pintype "passive"))
    )
    (net (code "69") (name "/PD6") (class "Default")
      (node (ref "U4") (pin "122") (pinfunction "PD6/FSMC_NWAIT_122") (pintype "passive"))
    )
    (net (code "70") (name "/PD7") (class "Default")
      (node (ref "U4") (pin "123") (pinfunction "PD7/FSMC_NE1/FSMC_NCE2_123") (pintype "passive"))
    )
    (net (code "71") (name "/PD8") (class "Default")
      (node (ref "LCD1") (pin "19") (pinfunction "19_19") (pintype "passive"))
      (node (ref "U4") (pin "77") (pinfunction "PD8/FSMC_D13_77") (pintype "passive"))
    )
    (net (code "72") (name "/PD9") (class "Default")
      (node (ref "LCD1") (pin "20") (pinfunction "20_20") (pintype "passive"))
      (node (ref "U4") (pin "78") (pinfunction "PD9/FSMC_D14_78") (pintype "passive"))
    )
    (net (code "73") (name "/PD10") (class "Default")
      (node (ref "LCD1") (pin "21") (pinfunction "21_21") (pintype "passive"))
      (node (ref "U4") (pin "79") (pinfunction "PD10/FSMC_D15_79") (pintype "passive"))
    )
    (net (code "74") (name "/PD11") (class "Default")
      (node (ref "U4") (pin "80") (pinfunction "PD11/FSMC_A16_80") (pintype "passive"))
    )
    (net (code "75") (name "/PD12") (class "Default")
      (node (ref "U4") (pin "81") (pinfunction "PD12/FSMC_A17_81") (pintype "passive"))
    )
    (net (code "76") (name "/PD13") (class "Default")
      (node (ref "U4") (pin "82") (pinfunction "PD13/FSMC_A18_82") (pintype "passive"))
    )
    (net (code "77") (name "/PD14") (class "Default")
      (node (ref "LCD1") (pin "6") (pinfunction "6_6") (pintype "passive"))
      (node (ref "U4") (pin "85") (pinfunction "PD14/FSMC_D0_85") (pintype "passive"))
    )
    (net (code "78") (name "/PD15") (class "Default")
      (node (ref "LCD1") (pin "7") (pinfunction "7_7") (pintype "passive"))
      (node (ref "U4") (pin "86") (pinfunction "PD15/FSMC_D1_86") (pintype "passive"))
    )
    (net (code "79") (name "/PE0") (class "Default")
      (node (ref "U4") (pin "141") (pinfunction "PE0/TIM4_ETR/FSMC_NBL0_141") (pintype "passive"))
    )
    (net (code "80") (name "/PE1") (class "Default")
      (node (ref "U4") (pin "142") (pinfunction "PE1/FSMC_NBL1_142") (pintype "passive"))
    )
    (net (code "81") (name "/PE2") (class "Default")
      (node (ref "U4") (pin "1") (pinfunction "PE2/TRACECK/FSMC_A23_1") (pintype "passive"))
    )
    (net (code "82") (name "/PE3") (class "Default")
      (node (ref "U4") (pin "2") (pinfunction "PE3/TRACED0/FSMC_A19_2") (pintype "passive"))
    )
    (net (code "83") (name "/PE4") (class "Default")
      (node (ref "U4") (pin "3") (pinfunction "PE4/TRACED1/FSMC_A20_3") (pintype "passive"))
    )
    (net (code "84") (name "/PE5") (class "Default")
      (node (ref "U4") (pin "4") (pinfunction "PE5/TRACED2/FSMC_A21_4") (pintype "passive"))
    )
    (net (code "85") (name "/PE6") (class "Default")
      (node (ref "U4") (pin "5") (pinfunction "PE6/TRACED3/FSMC_A22_5") (pintype "passive"))
    )
    (net (code "86") (name "/PE7") (class "Default")
      (node (ref "LCD1") (pin "10") (pinfunction "10_10") (pintype "passive"))
      (node (ref "U4") (pin "58") (pinfunction "PE7/FSMC_D4_58") (pintype "passive"))
    )
    (net (code "87") (name "/PE8") (class "Default")
      (node (ref "LCD1") (pin "11") (pinfunction "11_11") (pintype "passive"))
      (node (ref "U4") (pin "59") (pinfunction "PE8/FSMC_D5_59") (pintype "passive"))
    )
    (net (code "88") (name "/PE9") (class "Default")
      (node (ref "LCD1") (pin "12") (pinfunction "12_12") (pintype "passive"))
      (node (ref "U4") (pin "60") (pinfunction "PE9/FSMC_D6_60") (pintype "passive"))
    )
    (net (code "89") (name "/PE10") (class "Default")
      (node (ref "LCD1") (pin "13") (pinfunction "13_13") (pintype "passive"))
      (node (ref "U4") (pin "63") (pinfunction "PE10/FSMC_D7_63") (pintype "passive"))
    )
    (net (code "90") (name "/PE11") (class "Default")
      (node (ref "LCD1") (pin "14") (pinfunction "14_14") (pintype "passive"))
      (node (ref "U4") (pin "64") (pinfunction "PE11/FSMC_D8_64") (pintype "passive"))
    )
    (net (code "91") (name "/PE12") (class "Default")
      (node (ref "LCD1") (pin "15") (pinfunction "15_15") (pintype "passive"))
      (node (ref "U4") (pin "65") (pinfunction "PE12/FSMC_D9_65") (pintype "passive"))
    )
    (net (code "92") (name "/PE13") (class "Default")
      (node (ref "LCD1") (pin "16") (pinfunction "16_16") (pintype "passive"))
      (node (ref "U4") (pin "66") (pinfunction "PE13/FSMC_D10_66") (pintype "passive"))
    )
    (net (code "93") (name "/PE14") (class "Default")
      (node (ref "LCD1") (pin "17") (pinfunction "17_17") (pintype "passive"))
      (node (ref "U4") (pin "67") (pinfunction "PE14/FSMC_D11_67") (pintype "passive"))
    )
    (net (code "94") (name "/PE15") (class "Default")
      (node (ref "LCD1") (pin "18") (pinfunction "18_18") (pintype "passive"))
      (node (ref "U4") (pin "68") (pinfunction "PE15/FSMC_D12_68") (pintype "passive"))
    )
    (net (code "95") (name "/PF0") (class "Default")
      (node (ref "U4") (pin "10") (pinfunction "PF0/FSMC_A0_10") (pintype "passive"))
    )
    (net (code "96") (name "/PF1") (class "Default")
      (node (ref "U4") (pin "11") (pinfunction "PF1/FSMC_A1_11") (pintype "passive"))
    )
    (net (code "97") (name "/PF2") (class "Default")
      (node (ref "U4") (pin "12") (pinfunction "PF2/FSMC_A2_12") (pintype "passive"))
    )
    (net (code "98") (name "/PF3") (class "Default")
      (node (ref "U4") (pin "13") (pinfunction "PF3/FSMC_A3_13") (pintype "passive"))
    )
    (net (code "99") (name "/PF4") (class "Default")
      (node (ref "U4") (pin "14") (pinfunction "PF4/FSMC_A4_14") (pintype "passive"))
    )
    (net (code "100") (name "/PF5") (class "Default")
      (node (ref "R15") (pin "2") (pinfunction "2_2") (pintype "passive"))
      (node (ref "U4") (pin "15") (pinfunction "PF5/FSMC_A5_15") (pintype "passive"))
    )
    (net (code "101") (name "/PF6") (class "Default")
      (node (ref "U4") (pin "18") (pinfunction "PF6/ADC3_IN4/FSMC_NIORD_18") (pintype "passive"))
    )
    (net (code "102") (name "/PF7") (class "Default")
      (node (ref "U4") (pin "19") (pinfunction "PF7/ADC3_IN5/FSMC_NREG_19") (pintype "passive"))
    )
    (net (code "103") (name "/PF8") (class "Default")
      (node (ref "R21") (pin "2") (pinfunction "2_2") (pintype "passive"))
      (node (ref "U4") (pin "20") (pinfunction "PF8/ADC3_IN6/FSMC_NIOWR_20") (pintype "passive"))
    )
    (net (code "104") (name "/PF9") (class "Default")
      (node (ref "LCD1") (pin "30") (pinfunction "30_30") (pintype "passive"))
      (node (ref "U4") (pin "21") (pinfunction "PF9/ADC3_IN7/FSMC_CD_21") (pintype "passive"))
    )
    (net (code "105") (name "/PF10") (class "Default")
      (node (ref "LCD1") (pin "31") (pinfunction "31_31") (pintype "passive"))
      (node (ref "U4") (pin "22") (pinfunction "PF10/ADC3_IN8/FSMC_INTR_22") (pintype "passive"))
    )
    (net (code "106") (name "/PF11") (class "Default")
      (node (ref "LCD1") (pin "33") (pinfunction "33_33") (pintype "passive"))
      (node (ref "U4") (pin "49") (pinfunction "PF11/FSMC_NIOS16_49") (pintype "passive"))
    )
    (net (code "107") (name "/PF12") (class "Default")
      (node (ref "U4") (pin "50") (pinfunction "PF12/FSMC_A6_50") (pintype "passive"))
    )
    (net (code "108") (name "/PF13") (class "Default")
      (node (ref "U4") (pin "53") (pinfunction "PF13/FSMC_A7_53") (pintype "passive"))
    )
    (net (code "109") (name "/PF14") (class "Default")
      (node (ref "U4") (pin "54") (pinfunction "PF14/FSMC_A8_54") (pintype "passive"))
    )
    (net (code "110") (name "/PF15") (class "Default")
      (node (ref "U4") (pin "55") (pinfunction "PF15/FSMC_A9_55") (pintype "passive"))
    )
    (net (code "111") (name "/PG0") (class "Default")
      (node (ref "LCD1") (pin "2") (pinfunction "2_2") (pintype "passive"))
      (node (ref "U4") (pin "56") (pinfunction "PG0/FSMC_A10_56") (pintype "passive"))
    )
    (net (code "112") (name "/PG1") (class "Default")
      (node (ref "U4") (pin "57") (pinfunction "PG1/FSMC_A11_57") (pintype "passive"))
    )
    (net (code "113") (name "/PG2") (class "Default")
      (node (ref "U4") (pin "87") (pinfunction "PG2/FSMC_A12_87") (pintype "passive"))
    )
    (net (code "114") (name "/PG3") (class "Default")
      (node (ref "U4") (pin "88") (pinfunction "PG3/FSMC_A13_88") (pintype "passive"))
    )
    (net (code "115") (name "/PG4") (class "Default")
      (node (ref "U4") (pin "89") (pinfunction "PG4/FSMC_A14_89") (pintype "passive"))
    )
    (net (code "116") (name "/PG5") (class "Default")
      (node (ref "U4") (pin "90") (pinfunction "PG5/FSMC_A15_90") (pintype "passive"))
    )
    (net (code "117") (name "/PG6") (class "Default")
      (node (ref "U4") (pin "91") (pinfunction "PG6/FSMC_INT2_91") (pintype "passive"))
    )
    (net (code "118") (name "/PG7") (class "Default")
      (node (ref "U4") (pin "92") (pinfunction "PG7/FSMC_INT3_92") (pintype "passive"))
    )
    (net (code "119") (name "/PG8") (class "Default")
      (node (ref "U4") (pin "93") (pinfunction "PG8_93") (pintype "passive"))
    )
    (net (code "120") (name "/PG9") (class "Default")
      (node (ref "U4") (pin "124") (pinfunction "PG9/FSMC_NE2/FSMC_NCE3_124") (pintype "passive"))
    )
    (net (code "121") (name "/PG10") (class "Default")
      (node (ref "U4") (pin "125") (pinfunction "PG10/FSMC_NCE4_1/FSMC_NE3_125") (pintype "passive"))
    )
    (net (code "122") (name "/PG11") (class "Default")
      (node (ref "U4") (pin "126") (pinfunction "PG11/FSMC_NCE4_2_126") (pintype "passive"))
    )
    (net (code "123") (name "/PG12") (class "Default")
      (node (ref "LCD1") (pin "1") (pinfunction "1_1") (pintype "passive"))
      (node (ref "U4") (pin "127") (pinfunction "PG12/FSMC_NE4_127") (pintype "passive"))
    )
    (net (code "124") (name "/PG13") (class "Default")
      (node (ref "U4") (pin "128") (pinfunction "PG13/FSMC_A24_128") (pintype "passive"))
    )
    (net (code "125") (name "/PG14") (class "Default")
      (node (ref "U4") (pin "129") (pinfunction "PG14/FSMC_A25_129") (pintype "passive"))
    )
    (net (code "126") (name "/PG15") (class "Default")
      (node (ref "U4") (pin "132") (pinfunction "PG15_132") (pintype "passive"))
    )
    (net (code "127") (name "/SC1") (class "Default")
      (node (ref "R37") (pin "1") (pinfunction "1_1") (pintype "passive"))
      (node (ref "R43") (pin "2") (pinfunction "2_2") (pintype "passive"))
    )
    (net (code "128") (name "/SC2") (class "Default")
      (node (ref "R39") (pin "1") (pinfunction "1_1") (pintype "passive"))
      (node (ref "R45") (pin "2") (pinfunction "2_2") (pintype "passive"))
    )
    (net (code "129") (name "/SD") (class "Default")
      (node (ref "U10") (pin "3") (pinfunction "~{SD}_3") (pintype "input"))
      (node (ref "U5") (pin "3") (pinfunction "~{SD}_3") (pintype "input"))
      (node (ref "U6") (pin "3") (pinfunction "~{SD}_3") (pintype "input"))
      (node (ref "U9") (pin "3") (pinfunction "~{SD}_3") (pintype "input"))
    )
    (net (code "130") (name "/SR1") (class "Default")
      (node (ref "R36") (pin "1") (pinfunction "1_1") (pintype "passive"))
      (node (ref "R42") (pin "2") (pinfunction "2_2") (pintype "passive"))
    )
    (net (code "131") (name "/SR2") (class "Default")
      (node (ref "R38") (pin "1") (pinfunction "1_1") (pintype "passive"))
      (node (ref "R44") (pin "2") (pinfunction "2_2") (pintype "passive"))
    )
    (net (code "132") (name "/VCC3.3") (class "Default")
      (node (ref "LCD1") (pin "25") (pinfunction "25_25") (pintype "passive"))
    )
    (net (code "133") (name "CGND") (class "Default")
      (node (ref "BOOT1") (pin "5") (pinfunction "5_5") (pintype "passive"))
      (node (ref "BOOT1") (pin "6") (pinfunction "6_6") (pintype "passive"))
      (node (ref "BT1") (pin "2") (pinfunction "-_2") (pintype "passive"))
      (node (ref "C10") (pin "1") (pinfunction "1_1") (pintype "passive"))
      (node (ref "C11") (pin "2") (pinfunction "2_2") (pintype "passive"))
      (node (ref "C12") (pin "2") (pinfunction "2_2") (pintype "passive"))
      (node (ref "C13") (pin "2") (pinfunction "2_2") (pintype "passive"))
      (node (ref "C14") (pin "2") (pinfunction "2_2") (pintype "passive"))
      (node (ref "C15") (pin "2") (pinfunction "2_2") (pintype "passive"))
      (node (ref "C16") (pin "2") (pinfunction "2_2") (pintype "passive"))
      (node (ref "C17") (pin "2") (pinfunction "2_2") (pintype "passive"))
      (node (ref "C18") (pin "2") (pinfunction "2_2") (pintype "passive"))
      (node (ref "C19") (pin "2") (pinfunction "2_2") (pintype "passive"))
      (node (ref "C20") (pin "2") (pinfunction "2_2") (pintype "passive"))
      (node (ref "C21") (pin "2") (pinfunction "2_2") (pintype "passive"))
      (node (ref "C23") (pin "2") (pinfunction "2_2") (pintype "passive"))
      (node (ref "C24") (pin "1") (pinfunction "1_1") (pintype "passive"))
      (node (ref "C25") (pin "2") (pinfunction "2_2") (pintype "passive"))
      (node (ref "C26") (pin "2") (pinfunction "2_2") (pintype "passive"))
      (node (ref "C27") (pin "2") (pinfunction "2_2") (pintype "passive"))
      (node (ref "C28") (pin "2") (pinfunction "2_2") (pintype "passive"))
      (node (ref "C29") (pin "1") (pinfunction "1_1") (pintype "passive"))
      (node (ref "C30") (pin "2") (pinfunction "2_2") (pintype "passive"))
      (node (ref "C31") (pin "1") (pinfunction "1_1") (pintype "passive"))
      (node (ref "C34") (pin "1") (pinfunction "1_1") (pintype "passive"))
      (node (ref "C35") (pin "1") (pinfunction "1_1") (pintype "passive"))
      (node (ref "C36") (pin "1") (pinfunction "1_1") (pintype "passive"))
      (node (ref "C37") (pin "1") (pinfunction "1_1") (pintype "passive"))
      (node (ref "C38") (pin "2") (pinfunction "2_2") (pintype "passive"))
      (node (ref "C39") (pin "2") (pinfunction "2_2") (pintype "passive"))
      (node (ref "C4") (pin "2") (pinfunction "2_2") (pintype "passive"))
      (node (ref "C40") (pin "2") (pinfunction "2_2") (pintype "passive"))
      (node (ref "C41") (pin "2") (pinfunction "2_2") (pintype "passive"))
      (node (ref "C42") (pin "1") (pinfunction "1_1") (pintype "passive"))
      (node (ref "C43") (pin "2") (pinfunction "2_2") (pintype "passive"))
      (node (ref "C44") (pin "1") (pinfunction "1_1") (pintype "passive"))
      (node (ref "C45") (pin "2") (pinfunction "2_2") (pintype "passive"))
      (node (ref "C46") (pin "2") (pinfunction "2_2") (pintype "passive"))
      (node (ref "C47") (pin "2") (pinfunction "2_2") (pintype "passive"))
      (node (ref "C49") (pin "1") (pinfunction "1_1") (pintype "passive"))
      (node (ref "C5") (pin "2") (pinfunction "2_2") (pintype "passive"))
      (node (ref "C50") (pin "2") (pinfunction "2_2") (pintype "passive"))
      (node (ref "C51") (pin "2") (pinfunction "2_2") (pintype "passive"))
      (node (ref "C6") (pin "2") (pinfunction "2_2") (pintype "passive"))
      (node (ref "C7") (pin "2") (pinfunction "2_2") (pintype "passive"))
      (node (ref "C9") (pin "2") (pinfunction "2_2") (pintype "passive"))
      (node (ref "D3") (pin "2") (pinfunction "K_2") (pintype "passive"))
      (node (ref "J1") (pin "10") (pinfunction "10_10") (pintype "passive"))
      (node (ref "J1") (pin "12") (pinfunction "12_12") (pintype "passive"))
      (node (ref "J1") (pin "14") (pinfunction "14_14") (pintype "passive"))
      (node (ref "J1") (pin "16") (pinfunction "16_16") (pintype "passive"))
      (node (ref "J1") (pin "18") (pinfunction "18_18") (pintype "passive"))
      (node (ref "J1") (pin "20") (pinfunction "20_20") (pintype "passive"))
      (node (ref "J1") (pin "4") (pinfunction "4_4") (pintype "passive"))
      (node (ref "J1") (pin "6") (pinfunction "6_6") (pintype "passive"))
      (node (ref "J1") (pin "8") (pinfunction "8_8") (pintype "passive"))
      (node (ref "L3") (pin "2") (pinfunction "2_2") (pintype "passive"))
      (node (ref "LCD1") (pin "22") (pinfunction "22_22") (pintype "passive"))
      (node (ref "LCD1") (pin "26") (pinfunction "26_26") (pintype "passive"))
      (node (ref "LCD1") (pin "27") (pinfunction "27_27") (pintype "passive"))
      (node (ref "LD1") (pin "2") (pinfunction "K_2") (pintype "passive"))
      (node (ref "LD2") (pin "2") (pinfunction "K_2") (pintype "passive"))
      (node (ref "P1") (pin "5") (pinfunction "5_5") (pintype "passive"))
      (node (ref "P10") (pin "2") (pinfunction "2_2") (pintype "passive"))
      (node (ref "P13") (pin "3") (pinfunction "3_3") (pintype "passive"))
      (node (ref "P14") (pin "3") (pinfunction "3_3") (pintype "passive"))
      (node (ref "P2") (pin "3") (pinfunction "3_3") (pintype "passive"))
      (node (ref "P4") (pin "1") (pinfunction "1_1") (pintype "passive"))
      (node (ref "P8") (pin "2") (pinfunction "2_2") (pintype "passive"))
      (node (ref "P9") (pin "2") (pinfunction "2_2") (pintype "passive"))
      (node (ref "Q3") (pin "3") (pinfunction "S_3") (pintype "passive"))
      (node (ref "R12") (pin "1") (pinfunction "1_1") (pintype "passive"))
      (node (ref "R16") (pin "1") (pinfunction "1_1") (pintype "passive"))
      (node (ref "R17") (pin "1") (pinfunction "1_1") (pintype "passive"))
      (node (ref "R23") (pin "1") (pinfunction "1_1") (pintype "passive"))
      (node (ref "R28") (pin "2") (pinfunction "2_2") (pintype "passive"))
      (node (ref "R42") (pin "1") (pinfunction "1_1") (pintype "passive"))
      (node (ref "R43") (pin "1") (pinfunction "1_1") (pintype "passive"))
      (node (ref "R7") (pin "1") (pinfunction "1_1") (pintype "passive"))
      (node (ref "R8") (pin "1") (pinfunction "1_1") (pintype "passive"))
      (node (ref "S1") (pin "2") (pinfunction "2_2") (pintype "passive"))
      (node (ref "U1") (pin "1") (pinfunction "GND_1") (pintype "passive"))
      (node (ref "U10") (pin "4") (pinfunction "COM_4") (pintype "passive"))
      (node (ref "U2") (pin "1") (pinfunction "GND_1") (pintype "passive"))
      (node (ref "U3") (pin "1") (pinfunction "GND_1") (pintype "passive"))
      (node (ref "U4") (pin "107") (pinfunction "Vss_2_107") (pintype "passive"))
      (node (ref "U4") (pin "120") (pinfunction "Vss_10_120") (pintype "passive"))
      (node (ref "U4") (pin "130") (pinfunction "Vss_11_130") (pintype "passive"))
      (node (ref "U4") (pin "143") (pinfunction "Vss_3_143") (pintype "passive"))
      (node (ref "U4") (pin "16") (pinfunction "Vss_5_16") (pintype "passive"))
      (node (ref "U4") (pin "38") (pinfunction "Vss_4_38") (pintype "passive"))
      (node (ref "U4") (pin "51") (pinfunction "Vss_6_51") (pintype "passive"))
      (node (ref "U4") (pin "61") (pinfunction "Vss_7_61") (pintype "passive"))
      (node (ref "U4") (pin "71") (pinfunction "Vss_1_71") (pintype "passive"))
      (node (ref "U4") (pin "83") (pinfunction "Vss_8_83") (pintype "passive"))
      (node (ref "U4") (pin "94") (pinfunction "Vss_9_94") (pintype "passive"))
      (node (ref "U5") (pin "4") (pinfunction "COM_4") (pintype "passive"))
      (node (ref "U6") (pin "4") (pinfunction "COM_4") (pintype "passive"))
      (node (ref "U7") (pin "2") (pinfunction "GND_2") (pintype "power_in"))
      (node (ref "U8") (pin "3") (pinfunction "GND_3") (pintype "passive"))
      (node (ref "U9") (pin "4") (pinfunction "COM_4") (pintype "passive"))
      (node (ref "U9") (pin "6") (pinfunction "VS_6") (pintype "passive"))
      (node (ref "key1") (pin "1") (pinfunction "1_1") (pintype "passive"))
      (node (ref "key2") (pin "1") (pinfunction "1_1") (pintype "passive"))
    )
    (net (code "134") (name "Net-(BOOT1-Pad3)") (class "Default")
      (node (ref "BOOT1") (pin "3") (pinfunction "3_3") (pintype "passive"))
      (node (ref "R19") (pin "2") (pinfunction "2_2") (pintype "passive"))
    )
    (net (code "135") (name "Net-(BOOT1-Pad4)") (class "Default")
      (node (ref "BOOT1") (pin "4") (pinfunction "4_4") (pintype "passive"))
      (node (ref "R20") (pin "1") (pinfunction "1_1") (pintype "passive"))
    )
    (net (code "136") (name "Net-(BT1-+)") (class "Default")
      (node (ref "BT1") (pin "1") (pinfunction "+_1") (pintype "passive"))
      (node (ref "R34") (pin "1") (pinfunction "1_1") (pintype "passive"))
    )
    (net (code "137") (name "Net-(C34-Pad2)") (class "Default")
      (node (ref "C34") (pin "2") (pinfunction "2_2") (pintype "passive"))
      (node (ref "R27") (pin "2") (pinfunction "2_2") (pintype "passive"))
    )
    (net (code "138") (name "Net-(C44-Pad2)") (class "Default")
      (node (ref "C44") (pin "2") (pinfunction "2_2") (pintype "passive"))
      (node (ref "R32") (pin "1") (pinfunction "1_1") (pintype "passive"))
      (node (ref "X1") (pin "1") (pinfunction "1_1") (pintype "passive"))
    )
    (net (code "139") (name "Net-(C45-Pad1)") (class "Default")
      (node (ref "C45") (pin "1") (pinfunction "1_1") (pintype "passive"))
      (node (ref "R33") (pin "1") (pinfunction "1_1") (pintype "passive"))
      (node (ref "X1") (pin "4") (pinfunction "4_4") (pintype "passive"))
    )
    (net (code "140") (name "Net-(D1-K)") (class "Default")
      (node (ref "C32") (pin "1") (pinfunction "1_1") (pintype "passive"))
      (node (ref "D1") (pin "2") (pinfunction "K_2") (pintype "passive"))
      (node (ref "U5") (pin "8") (pinfunction "VB_8") (pintype "passive"))
    )
    (net (code "141") (name "Net-(D2-K)") (class "Default")
      (node (ref "C33") (pin "1") (pinfunction "1_1") (pintype "passive"))
      (node (ref "D2") (pin "2") (pinfunction "K_2") (pintype "passive"))
      (node (ref "U6") (pin "8") (pinfunction "VB_8") (pintype "passive"))
    )
    (net (code "142") (name "Net-(D3-A)") (class "Default")
      (node (ref "D3") (pin "1") (pinfunction "A_1") (pintype "passive"))
      (node (ref "R24") (pin "1") (pinfunction "1_1") (pintype "passive"))
    )
    (net (code "143") (name "Net-(D4-A)") (class "Default")
      (node (ref "D4") (pin "1") (pinfunction "A_1") (pintype "passive"))
      (node (ref "L6") (pin "2") (pinfunction "2_2") (pintype "passive"))
      (node (ref "U8") (pin "4") (pinfunction "switch_4") (pintype "passive"))
    )
    (net (code "144") (name "Net-(D5-A)") (class "Default")
      (node (ref "D5") (pin "1") (pinfunction "A_1") (pintype "passive"))
      (node (ref "L5") (pin "1") (pinfunction "1_1") (pintype "passive"))
      (node (ref "Q3") (pin "2") (pinfunction "D_2") (pintype "passive"))
    )
    (net (code "145") (name "Net-(D6-K)") (class "Default")
      (node (ref "C40") (pin "1") (pinfunction "1_1") (pintype "passive"))
      (node (ref "D6") (pin "2") (pinfunction "K_2") (pintype "passive"))
      (node (ref "U9") (pin "8") (pinfunction "VB_8") (pintype "passive"))
    )
    (net (code "146") (name "Net-(D7-K)") (class "Default")
      (node (ref "C48") (pin "1") (pinfunction "1_1") (pintype "passive"))
      (node (ref "D7") (pin "2") (pinfunction "K_2") (pintype "passive"))
      (node (ref "U10") (pin "8") (pinfunction "VB_8") (pintype "passive"))
    )
    (net (code "147") (name "Net-(D8-K)") (class "Default")
      (node (ref "C48") (pin "2") (pinfunction "2_2") (pintype "passive"))
      (node (ref "D8") (pin "2") (pinfunction "K_2") (pintype "passive"))
      (node (ref "L7") (pin "2") (pinfunction "2_2") (pintype "passive"))
      (node (ref "Q4") (pin "3") (pinfunction "S_3") (pintype "passive"))
      (node (ref "U10") (pin "6") (pinfunction "VS_6") (pintype "passive"))
    )
    (net (code "148") (name "Net-(J1-Pad11)") (class "Default")
      (node (ref "J1") (pin "11") (pinfunction "11_11") (pintype "passive"))
      (node (ref "R9") (pin "1") (pinfunction "1_1") (pintype "passive"))
    )
    (net (code "149") (name "Net-(J1-Pad19)") (class "Default")
      (node (ref "J1") (pin "19") (pinfunction "19_19") (pintype "passive"))
      (node (ref "R13") (pin "1") (pinfunction "1_1") (pintype "passive"))
    )
    (net (code "150") (name "Net-(L5-Pad2)") (class "Default")
      (node (ref "L5") (pin "2") (pinfunction "2_2") (pintype "passive"))
      (node (ref "P6") (pin "1") (pinfunction "1_1") (pintype "passive"))
    )
    (net (code "151") (name "Net-(LD1-A)") (class "Default")
      (node (ref "LD1") (pin "1") (pinfunction "A_1") (pintype "passive"))
      (node (ref "R15") (pin "1") (pinfunction "1_1") (pintype "passive"))
    )
    (net (code "152") (name "Net-(LD2-A)") (class "Default")
      (node (ref "LD2") (pin "1") (pinfunction "A_1") (pintype "passive"))
      (node (ref "R21") (pin "1") (pinfunction "1_1") (pintype "passive"))
    )
    (net (code "153") (name "Net-(P3-Pad1)") (class "Default")
      (node (ref "P3") (pin "1") (pinfunction "1_1") (pintype "passive"))
      (node (ref "P3") (pin "2") (pinfunction "2_2") (pintype "passive"))
      (node (ref "P4") (pin "2") (pinfunction "2_2") (pintype "passive"))
    )
    (net (code "154") (name "Net-(Q1-D)") (class "Default")
      (node (ref "P8") (pin "1") (pinfunction "1_1") (pintype "passive"))
      (node (ref "Q1") (pin "2") (pinfunction "D_2") (pintype "passive"))
    )
    (net (code "155") (name "Net-(Q1-G)") (class "Default")
      (node (ref "Q1") (pin "1") (pinfunction "G_1") (pintype "passive"))
      (node (ref "R25") (pin "2") (pinfunction "2_2") (pintype "passive"))
    )
    (net (code "156") (name "Net-(Q1-S)") (class "Default")
      (node (ref "C32") (pin "2") (pinfunction "2_2") (pintype "passive"))
      (node (ref "P5") (pin "2") (pinfunction "2_2") (pintype "passive"))
      (node (ref "Q1") (pin "3") (pinfunction "S_3") (pintype "passive"))
      (node (ref "U5") (pin "6") (pinfunction "VS_6") (pintype "passive"))
    )
    (net (code "157") (name "Net-(Q2-D)") (class "Default")
      (node (ref "P7") (pin "1") (pinfunction "1_1") (pintype "passive"))
      (node (ref "P7") (pin "2") (pinfunction "2_2") (pintype "passive"))
      (node (ref "Q2") (pin "2") (pinfunction "D_2") (pintype "passive"))
    )
    (net (code "158") (name "Net-(Q2-G)") (class "Default")
      (node (ref "Q2") (pin "1") (pinfunction "G_1") (pintype "passive"))
      (node (ref "R26") (pin "2") (pinfunction "2_2") (pintype "passive"))
    )
    (net (code "159") (name "Net-(Q2-S)") (class "Default")
      (node (ref "C33") (pin "2") (pinfunction "2_2") (pintype "passive"))
      (node (ref "P6") (pin "2") (pinfunction "2_2") (pintype "passive"))
      (node (ref "Q2") (pin "3") (pinfunction "S_3") (pintype "passive"))
      (node (ref "U6") (pin "6") (pinfunction "VS_6") (pintype "passive"))
    )
    (net (code "160") (name "Net-(Q3-G)") (class "Default")
      (node (ref "Q3") (pin "1") (pinfunction "G_1") (pintype "passive"))
      (node (ref "R30") (pin "2") (pinfunction "2_2") (pintype "passive"))
    )
    (net (code "161") (name "Net-(Q4-G)") (class "Default")
      (node (ref "Q4") (pin "1") (pinfunction "G_1") (pintype "passive"))
      (node (ref "R41") (pin "2") (pinfunction "2_2") (pintype "passive"))
    )
    (net (code "162") (name "Net-(R10-Pad1)") (class "Default")
      (node (ref "R10") (pin "1") (pinfunction "1_1") (pintype "passive"))
      (node (ref "R11") (pin "1") (pinfunction "1_1") (pintype "passive"))
      (node (ref "R12") (pin "2") (pinfunction "2_2") (pintype "passive"))
    )
    (net (code "163") (name "Net-(R18-Pad1)") (class "Default")
      (node (ref "R18") (pin "1") (pinfunction "1_1") (pintype "passive"))
      (node (ref "R22") (pin "1") (pinfunction "1_1") (pintype "passive"))
      (node (ref "R23") (pin "2") (pinfunction "2_2") (pintype "passive"))
    )
    (net (code "164") (name "Net-(U2-Vad)") (class "Default")
      (node (ref "C10") (pin "2") (pinfunction "2_2") (pintype "passive"))
      (node (ref "C9") (pin "1") (pinfunction "1_1") (pintype "passive"))
      (node (ref "R11") (pin "2") (pinfunction "2_2") (pintype "passive"))
      (node (ref "U2") (pin "4") (pinfunction "Vad_4") (pintype "passive"))
    )
    (net (code "165") (name "Net-(U2-Vsens+)") (class "Default")
      (node (ref "C8") (pin "2") (pinfunction "2_2") (pintype "passive"))
      (node (ref "R6") (pin "1") (pinfunction "1_1") (pintype "passive"))
      (node (ref "R7") (pin "2") (pinfunction "2_2") (pintype "passive"))
      (node (ref "U2") (pin "2") (pinfunction "Vsens+_2") (pintype "passive"))
    )
    (net (code "166") (name "Net-(U2-Vsens-)") (class "Default")
      (node (ref "C8") (pin "1") (pinfunction "1_1") (pintype "passive"))
      (node (ref "R8") (pin "2") (pinfunction "2_2") (pintype "passive"))
      (node (ref "U2") (pin "3") (pinfunction "Vsens-_3") (pintype "passive"))
    )
    (net (code "167") (name "Net-(U3-Vad)") (class "Default")
      (node (ref "C23") (pin "1") (pinfunction "1_1") (pintype "passive"))
      (node (ref "C24") (pin "2") (pinfunction "2_2") (pintype "passive"))
      (node (ref "R22") (pin "2") (pinfunction "2_2") (pintype "passive"))
      (node (ref "U3") (pin "4") (pinfunction "Vad_4") (pintype "passive"))
    )
    (net (code "168") (name "Net-(U3-Vsens+)") (class "Default")
      (node (ref "C22") (pin "2") (pinfunction "2_2") (pintype "passive"))
      (node (ref "R14") (pin "1") (pinfunction "1_1") (pintype "passive"))
      (node (ref "R16") (pin "2") (pinfunction "2_2") (pintype "passive"))
      (node (ref "U3") (pin "2") (pinfunction "Vsens+_2") (pintype "passive"))
    )
    (net (code "169") (name "Net-(U3-Vsens-)") (class "Default")
      (node (ref "C22") (pin "1") (pinfunction "1_1") (pintype "passive"))
      (node (ref "R17") (pin "2") (pinfunction "2_2") (pintype "passive"))
      (node (ref "U3") (pin "3") (pinfunction "Vsens-_3") (pintype "passive"))
    )
    (net (code "170") (name "Net-(U4-OSC_IN)") (class "Default")
      (node (ref "C43") (pin "1") (pinfunction "1_1") (pintype "passive"))
      (node (ref "R35") (pin "2") (pinfunction "2_2") (pintype "passive"))
      (node (ref "U4") (pin "23") (pinfunction "OSC_IN_23") (pintype "passive"))
      (node (ref "X2") (pin "2") (pinfunction "OSC2_2") (pintype "passive"))
    )
    (net (code "171") (name "Net-(U4-OSC_OUT)") (class "Default")
      (node (ref "C46") (pin "1") (pinfunction "1_1") (pintype "passive"))
      (node (ref "R35") (pin "1") (pinfunction "1_1") (pintype "passive"))
      (node (ref "U4") (pin "24") (pinfunction "OSC_OUT_24") (pintype "passive"))
      (node (ref "X2") (pin "1") (pinfunction "OSC1_1") (pintype "passive"))
    )
    (net (code "172") (name "Net-(U4-VBAT)") (class "Default")
      (node (ref "R31") (pin "2") (pinfunction "2_2") (pintype "passive"))
      (node (ref "R34") (pin "2") (pinfunction "2_2") (pintype "passive"))
      (node (ref "U4") (pin "6") (pinfunction "VBAT_6") (pintype "passive"))
    )
    (net (code "173") (name "Net-(U5-LO)") (class "Default")
      (node (ref "R25") (pin "1") (pinfunction "1_1") (pintype "passive"))
      (node (ref "U5") (pin "5") (pinfunction "LO_5") (pintype "output"))
    )
    (net (code "174") (name "Net-(U6-LO)") (class "Default")
      (node (ref "R26") (pin "1") (pinfunction "1_1") (pintype "passive"))
      (node (ref "U6") (pin "5") (pinfunction "LO_5") (pintype "output"))
    )
    (net (code "175") (name "Net-(U8-comp)") (class "Default")
      (node (ref "R27") (pin "1") (pinfunction "1_1") (pintype "passive"))
      (node (ref "U8") (pin "1") (pinfunction "comp_1") (pintype "passive"))
    )
    (net (code "176") (name "Net-(U8-feedback)") (class "Default")
      (node (ref "R28") (pin "1") (pinfunction "1_1") (pintype "passive"))
      (node (ref "R29") (pin "2") (pinfunction "2_2") (pintype "passive"))
      (node (ref "U8") (pin "2") (pinfunction "feedback_2") (pintype "passive"))
    )
    (net (code "177") (name "Net-(U9-LO)") (class "Default")
      (node (ref "R30") (pin "1") (pinfunction "1_1") (pintype "passive"))
      (node (ref "U9") (pin "5") (pinfunction "LO_5") (pintype "output"))
    )
    (net (code "178") (name "Net-(U10-HO)") (class "Default")
      (node (ref "R41") (pin "1") (pinfunction "1_1") (pintype "passive"))
      (node (ref "U10") (pin "7") (pinfunction "HO_7") (pintype "output"))
    )
    (net (code "179") (name "VCC7.2") (class "Default")
      (node (ref "C30") (pin "1") (pinfunction "1_1") (pintype "passive"))
      (node (ref "C35") (pin "2") (pinfunction "2_2") (pintype "passive"))
      (node (ref "C36") (pin "2") (pinfunction "2_2") (pintype "passive"))
      (node (ref "C37") (pin "2") (pinfunction "2_2") (pintype "passive"))
      (node (ref "L6") (pin "1") (pinfunction "1_1") (pintype "passive"))
      (node (ref "P3") (pin "3") (pinfunction "3_3") (pintype "passive"))
      (node (ref "R24") (pin "2") (pinfunction "2_2") (pintype "passive"))
      (node (ref "U7") (pin "1") (pinfunction "IN_1") (pintype "power_in"))
      (node (ref "U8") (pin "5") (pinfunction "Vin_5") (pintype "passive"))
    )
    (net (code "180") (name "VCC12") (class "Default")
      (node (ref "C27") (pin "1") (pinfunction "1_1") (pintype "passive"))
      (node (ref "C28") (pin "1") (pinfunction "1_1") (pintype "passive"))
      (node (ref "C38") (pin "1") (pinfunction "1_1") (pintype "passive"))
      (node (ref "C39") (pin "1") (pinfunction "1_1") (pintype "passive"))
      (node (ref "C47") (pin "1") (pinfunction "1_1") (pintype "passive"))
      (node (ref "D1") (pin "1") (pinfunction "A_1") (pintype "passive"))
      (node (ref "D2") (pin "1") (pinfunction "A_1") (pintype "passive"))
      (node (ref "D4") (pin "2") (pinfunction "K_2") (pintype "passive"))
      (node (ref "D6") (pin "1") (pinfunction "A_1") (pintype "passive"))
      (node (ref "D7") (pin "1") (pinfunction "A_1") (pintype "passive"))
      (node (ref "R29") (pin "1") (pinfunction "1_1") (pintype "passive"))
      (node (ref "U10") (pin "1") (pinfunction "VCC_1") (pintype "passive"))
      (node (ref "U5") (pin "1") (pinfunction "VCC_1") (pintype "passive"))
      (node (ref "U6") (pin "1") (pinfunction "VCC_1") (pintype "passive"))
      (node (ref "U9") (pin "1") (pinfunction "VCC_1") (pintype "passive"))
    )
    (net (code "181") (name "VDDA") (class "Default")
      (node (ref "C1") (pin "1") (pinfunction "1_1") (pintype "passive"))
      (node (ref "L1") (pin "1") (pinfunction "1_1") (pintype "passive"))
      (node (ref "L2") (pin "2") (pinfunction "2_2") (pintype "passive"))
      (node (ref "U4") (pin "33") (pinfunction "VDDA_33") (pintype "passive"))
    )
    (net (code "182") (name "VREF+") (class "Default")
      (node (ref "C2") (pin "1") (pinfunction "1_1") (pintype "passive"))
      (node (ref "C3") (pin "1") (pinfunction "1_1") (pintype "passive"))
      (node (ref "L2") (pin "1") (pinfunction "1_1") (pintype "passive"))
      (node (ref "U4") (pin "32") (pinfunction "Vref+_32") (pintype "passive"))
    )
    (net (code "183") (name "VREF-") (class "Default")
      (node (ref "C2") (pin "2") (pinfunction "2_2") (pintype "passive"))
      (node (ref "C3") (pin "2") (pinfunction "2_2") (pintype "passive"))
      (node (ref "L4") (pin "1") (pinfunction "1_1") (pintype "passive"))
      (node (ref "U4") (pin "31") (pinfunction "Vref-_31") (pintype "passive"))
    )
    (net (code "184") (name "VSSA") (class "Default")
      (node (ref "C1") (pin "2") (pinfunction "2_2") (pintype "passive"))
      (node (ref "L3") (pin "1") (pinfunction "1_1") (pintype "passive"))
      (node (ref "L4") (pin "2") (pinfunction "2_2") (pintype "passive"))
      (node (ref "U4") (pin "30") (pinfunction "VSSA_30") (pintype "passive"))
    )
    (net (code "185") (name "unconnected-(J1-Pad17)") (class "Default")
      (node (ref "J1") (pin "17") (pinfunction "17_17") (pintype "passive"))
    )
    (net (code "186") (name "unconnected-(LCD1-Pad32)") (class "Default")
      (node (ref "LCD1") (pin "32") (pinfunction "32_32") (pintype "passive"))
    )
    (net (code "187") (name "unconnected-(P1-Pad1)") (class "Default")
      (node (ref "P1") (pin "1") (pinfunction "1_1") (pintype "passive"))
    )
    (net (code "188") (name "unconnected-(P1-Pad2)") (class "Default")
      (node (ref "P1") (pin "2") (pinfunction "2_2") (pintype "passive"))
    )
    (net (code "189") (name "unconnected-(U2-DQ-Pad8)") (class "Default")
      (node (ref "U2") (pin "8") (pinfunction "DQ_8") (pintype "passive"))
    )
    (net (code "190") (name "unconnected-(U2-NC-Pad6)") (class "Default")
      (node (ref "U2") (pin "6") (pinfunction "NC_6") (pintype "passive"))
    )
    (net (code "191") (name "unconnected-(U2-NC-Pad7)") (class "Default")
      (node (ref "U2") (pin "7") (pinfunction "NC_7") (pintype "passive"))
    )
    (net (code "192") (name "unconnected-(U3-DQ-Pad8)") (class "Default")
      (node (ref "U3") (pin "8") (pinfunction "DQ_8") (pintype "passive"))
    )
    (net (code "193") (name "unconnected-(U3-NC-Pad6)") (class "Default")
      (node (ref "U3") (pin "6") (pinfunction "NC_6") (pintype "passive"))
    )
    (net (code "194") (name "unconnected-(U3-NC-Pad7)") (class "Default")
      (node (ref "U3") (pin "7") (pinfunction "NC_7") (pintype "passive"))
    )
    (net (code "195") (name "unconnected-(U4-NC-Pad106)") (class "Default")
      (node (ref "U4") (pin "106") (pinfunction "NC_106") (pintype "passive"))
    )
    (net (code "196") (name "unconnected-(U5-HO-Pad7)") (class "Default")
      (node (ref "U5") (pin "7") (pinfunction "HO_7") (pintype "output"))
    )
    (net (code "197") (name "unconnected-(U5-IN-Pad2)") (class "Default")
      (node (ref "U5") (pin "2") (pinfunction "IN_2") (pintype "input"))
    )
    (net (code "198") (name "unconnected-(U6-HO-Pad7)") (class "Default")
      (node (ref "U6") (pin "7") (pinfunction "HO_7") (pintype "output"))
    )
    (net (code "199") (name "unconnected-(U6-IN-Pad2)") (class "Default")
      (node (ref "U6") (pin "2") (pinfunction "IN_2") (pintype "input"))
    )
    (net (code "200") (name "unconnected-(U9-HO-Pad7)") (class "Default")
      (node (ref "U9") (pin "7") (pinfunction "HO_7") (pintype "output"))
    )
    (net (code "201") (name "unconnected-(U10-LO-Pad5)") (class "Default")
      (node (ref "U10") (pin "5") (pinfunction "LO_5") (pintype "output"))
    )
    (net (code "202") (name "unconnected-(X1-Pad2)") (class "Default")
      (node (ref "X1") (pin "2") (pinfunction "2_2") (pintype "passive"))
    )
    (net (code "203") (name "unconnected-(X1-Pad3)") (class "Default")
      (node (ref "X1") (pin "3") (pinfunction "3_3") (pintype "passive"))
    )
  )
)
